# sch_knx-valve-control_v1_2.net
KiCad netlist of a schematic drawn in EasyEDA
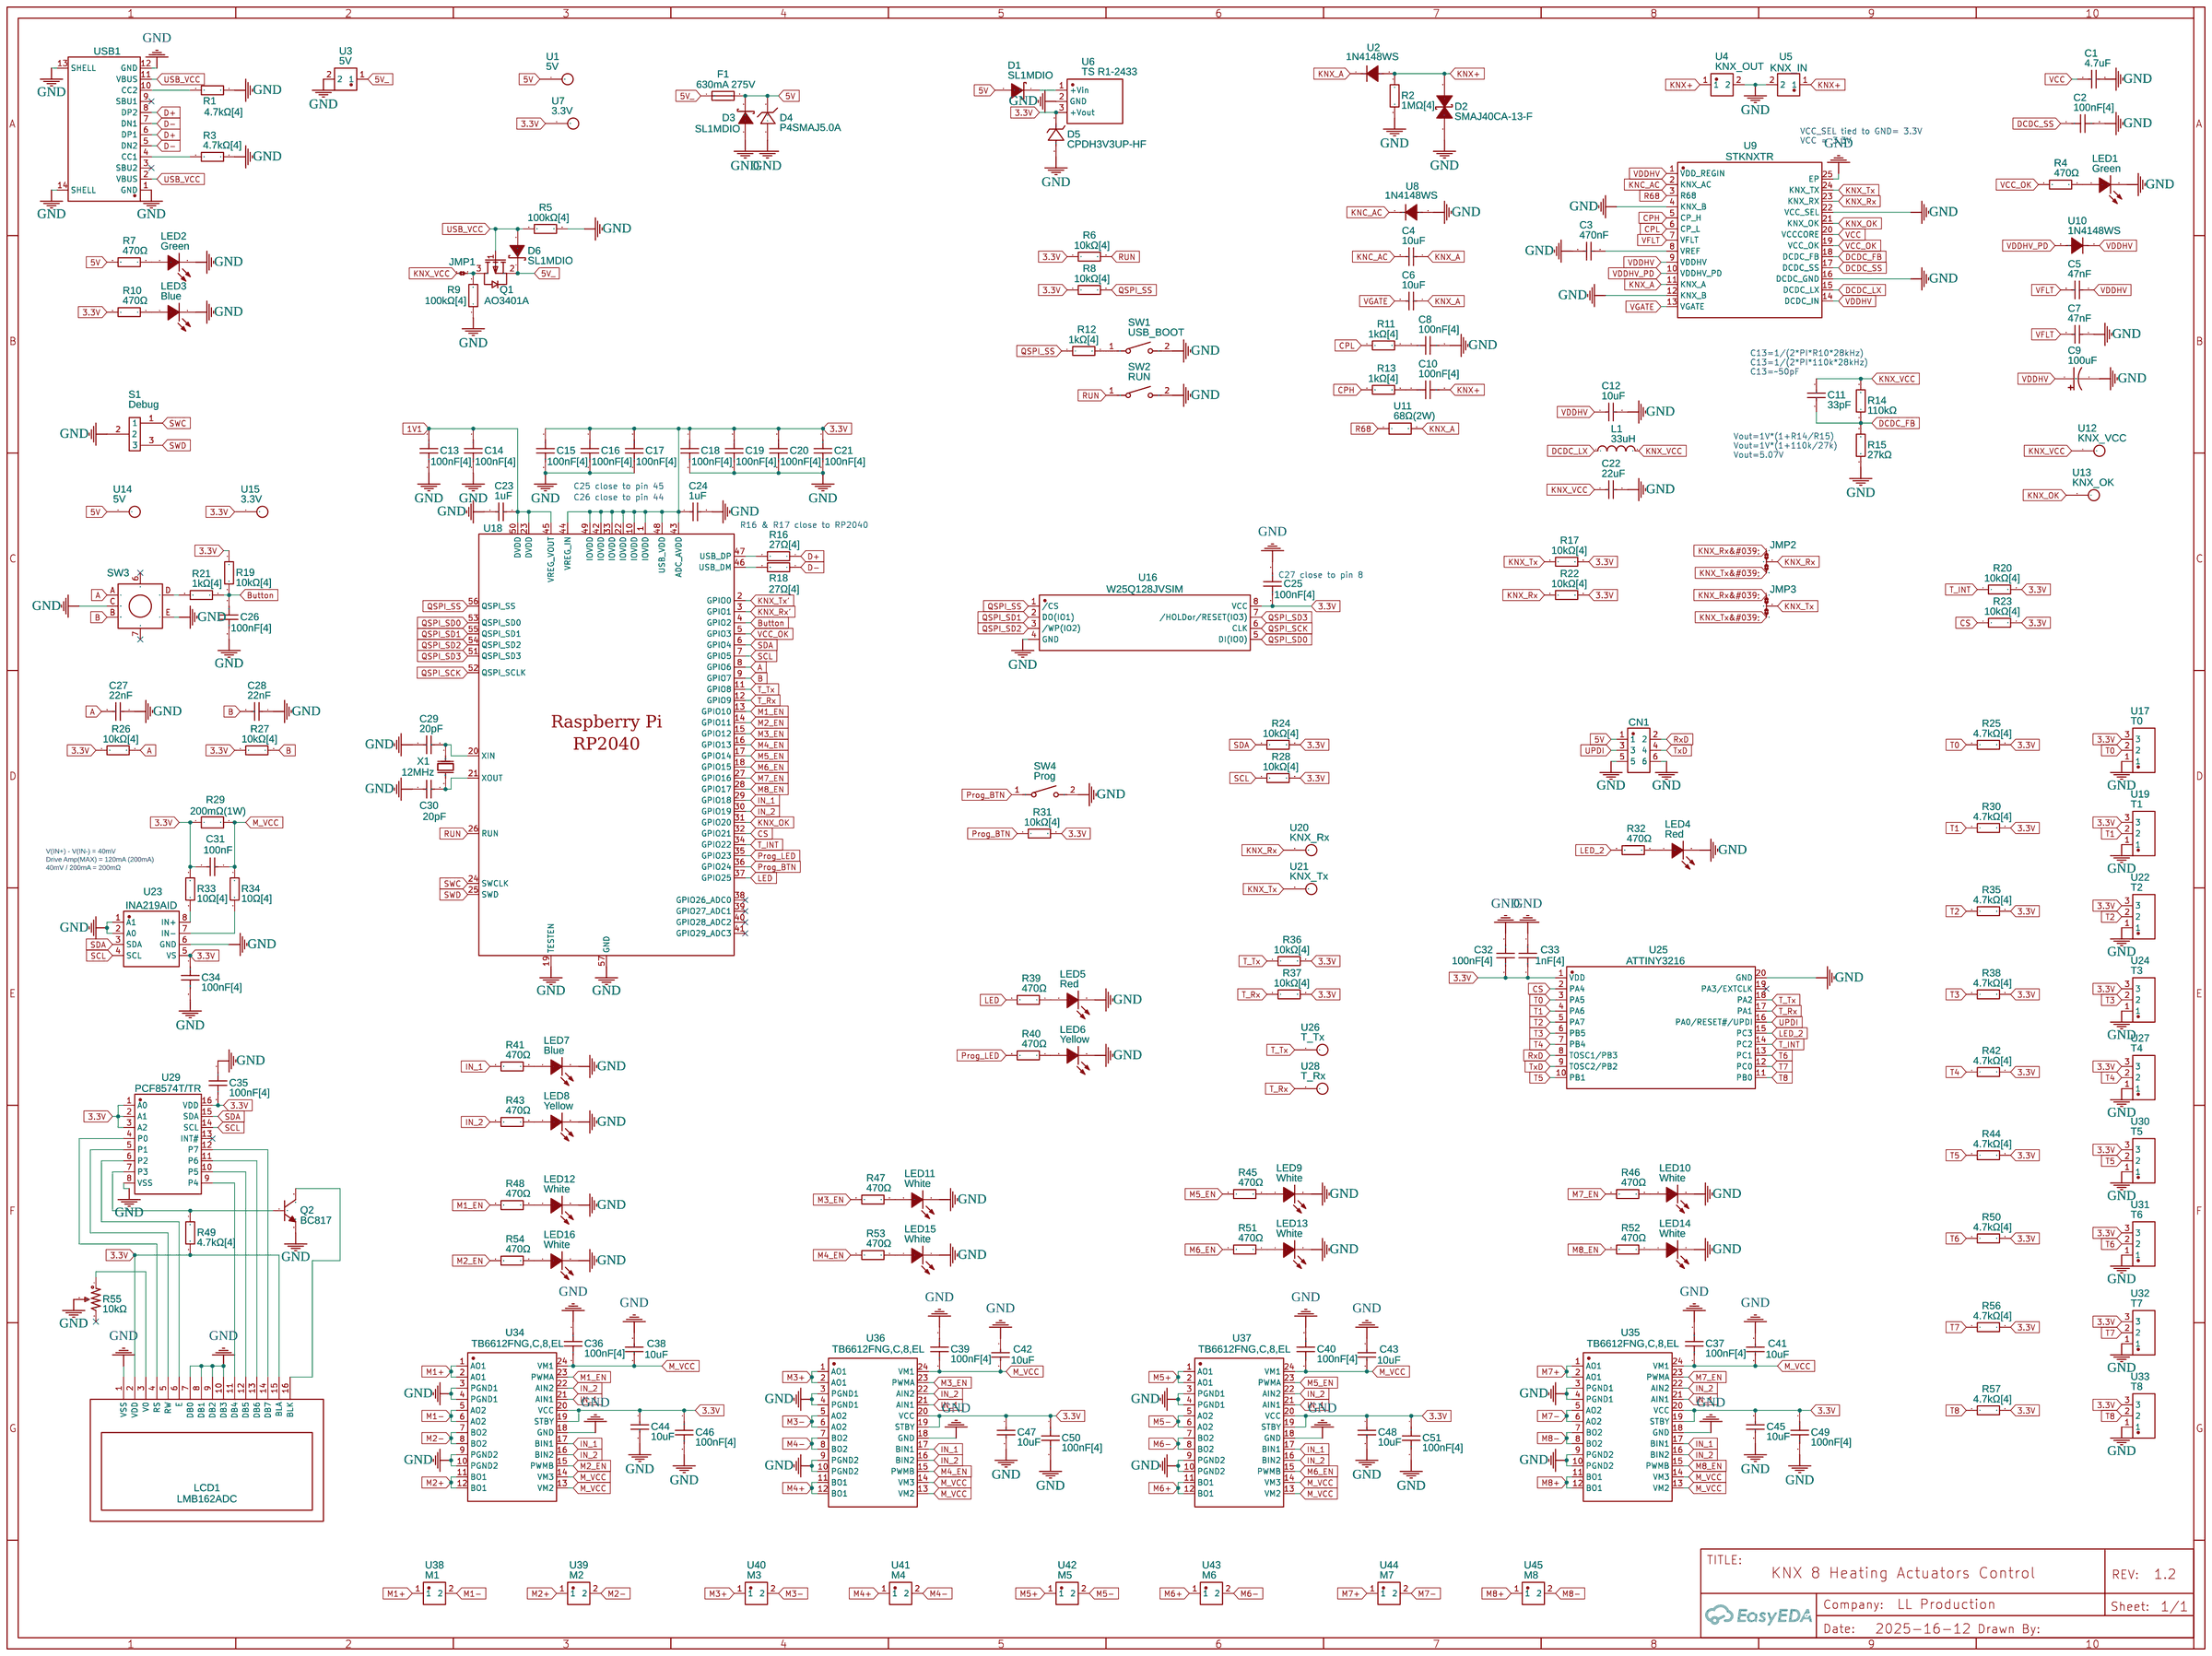
[diagram p0: schematic sheet]

(export (version "E")
  (design (tool "Eeschema 10.0.6"))
  (components
    (comp (ref "C1")
      (value "4.7uF")
      (fields (field (name "Manufacturer Part") "CC0603KRX7R9BB103") (field (name "Manufacturer") "YAGEO"))
      (libsource (lib "") (part "CC0603KRX7R9BB103_2"))
    )
    (comp (ref "C2")
      (value "100nF[4]")
      (fields
        (field (name "Manufacturer Part") "GRM155R71H104KE14D")
        (field (name "Manufacturer") "muRata(村田)")
      )
      (libsource (lib "") (part "GRM155R71H104KE14D_1"))
    )
    (comp (ref "C3")
      (value "470nF")
      (fields (field (name "Manufacturer Part") "CC0603KRX7R9BB103") (field (name "Manufacturer") "YAGEO"))
      (libsource (lib "") (part "CC0603KRX7R9BB103_1"))
    )
    (comp (ref "C4")
      (value "10uF")
      (fields (field (name "Manufacturer Part") "CC0603KRX7R9BB103") (field (name "Manufacturer") "YAGEO"))
      (libsource (lib "") (part "CC0603KRX7R9BB103_2"))
    )
    (comp (ref "C5")
      (value "47nF")
      (fields (field (name "Manufacturer Part") "CC0603KRX7R9BB103") (field (name "Manufacturer") "YAGEO"))
      (libsource (lib "") (part "CC0603KRX7R9BB103_2"))
    )
    (comp (ref "C6")
      (value "10uF")
      (fields (field (name "Manufacturer Part") "CC0603KRX7R9BB103") (field (name "Manufacturer") "YAGEO"))
      (libsource (lib "") (part "CC0603KRX7R9BB103_2"))
    )
    (comp (ref "C7")
      (value "47nF")
      (fields (field (name "Manufacturer Part") "CC0603KRX7R9BB103") (field (name "Manufacturer") "YAGEO"))
      (libsource (lib "") (part "CC0603KRX7R9BB103_2"))
    )
    (comp (ref "C8")
      (value "100nF[4]")
      (fields
        (field (name "Manufacturer Part") "GRM155R71H104KE14D")
        (field (name "Manufacturer") "muRata(村田)")
      )
      (libsource (lib "") (part "GRM155R71H104KE14D_1"))
    )
    (comp (ref "C9")
      (value "100uF")
      (fields (field (name "Manufacturer Part") "VEJ101M1HTR-0810") (field (name "Manufacturer") "Lelon(立隆)"))
      (libsource (lib "") (part "VEJ101M1HTR-0810"))
    )
    (comp (ref "C10")
      (value "100nF[4]")
      (fields
        (field (name "Manufacturer Part") "GRM155R71H104KE14D")
        (field (name "Manufacturer") "muRata(村田)")
      )
      (libsource (lib "") (part "GRM155R71H104KE14D_1"))
    )
    (comp (ref "C11")
      (value "33pF")
      (fields (field (name "Manufacturer Part") "CC0603KRX7R9BB103") (field (name "Manufacturer") "YAGEO"))
      (libsource (lib "") (part "CC0603KRX7R9BB103"))
    )
    (comp (ref "C12")
      (value "10uF")
      (fields (field (name "Manufacturer Part") "CC0603KRX7R9BB103") (field (name "Manufacturer") "YAGEO"))
      (libsource (lib "") (part "CC0603KRX7R9BB103_1"))
    )
    (comp (ref "C13")
      (value "100nF[4]")
      (fields
        (field (name "Manufacturer Part") "GRM155R71H104KE14D")
        (field (name "Manufacturer") "muRata(村田)")
      )
      (libsource (lib "") (part "GRM155R71H104KE14D"))
    )
    (comp (ref "C14")
      (value "100nF[4]")
      (fields
        (field (name "Manufacturer Part") "GRM155R71H104KE14D")
        (field (name "Manufacturer") "muRata(村田)")
      )
      (libsource (lib "") (part "GRM155R71H104KE14D"))
    )
    (comp (ref "C15")
      (value "100nF[4]")
      (fields
        (field (name "Manufacturer Part") "GRM155R71H104KE14D")
        (field (name "Manufacturer") "muRata(村田)")
      )
      (libsource (lib "") (part "GRM155R71H104KE14D"))
    )
    (comp (ref "C16")
      (value "100nF[4]")
      (fields
        (field (name "Manufacturer Part") "GRM155R71H104KE14D")
        (field (name "Manufacturer") "muRata(村田)")
      )
      (libsource (lib "") (part "GRM155R71H104KE14D"))
    )
    (comp (ref "C17")
      (value "100nF[4]")
      (fields
        (field (name "Manufacturer Part") "GRM155R71H104KE14D")
        (field (name "Manufacturer") "muRata(村田)")
      )
      (libsource (lib "") (part "GRM155R71H104KE14D"))
    )
    (comp (ref "C18")
      (value "100nF[4]")
      (fields
        (field (name "Manufacturer Part") "GRM155R71H104KE14D")
        (field (name "Manufacturer") "muRata(村田)")
      )
      (libsource (lib "") (part "GRM155R71H104KE14D"))
    )
    (comp (ref "C19")
      (value "100nF[4]")
      (fields
        (field (name "Manufacturer Part") "GRM155R71H104KE14D")
        (field (name "Manufacturer") "muRata(村田)")
      )
      (libsource (lib "") (part "GRM155R71H104KE14D"))
    )
    (comp (ref "C20")
      (value "100nF[4]")
      (fields
        (field (name "Manufacturer Part") "GRM155R71H104KE14D")
        (field (name "Manufacturer") "muRata(村田)")
      )
      (libsource (lib "") (part "GRM155R71H104KE14D"))
    )
    (comp (ref "C21")
      (value "100nF[4]")
      (fields
        (field (name "Manufacturer Part") "GRM155R71H104KE14D")
        (field (name "Manufacturer") "muRata(村田)")
      )
      (libsource (lib "") (part "GRM155R71H104KE14D"))
    )
    (comp (ref "C22")
      (value "22uF")
      (fields (field (name "Manufacturer Part") "CC0603KRX7R9BB103") (field (name "Manufacturer") "YAGEO"))
      (libsource (lib "") (part "CC0603KRX7R9BB103_1"))
    )
    (comp (ref "C23")
      (value "1uF")
      (fields (field (name "Manufacturer Part") "CC0603KRX7R9BB103") (field (name "Manufacturer") "YAGEO"))
      (libsource (lib "") (part "CC0603KRX7R9BB103_1"))
    )
    (comp (ref "C24")
      (value "1uF")
      (fields (field (name "Manufacturer Part") "CC0603KRX7R9BB103") (field (name "Manufacturer") "YAGEO"))
      (libsource (lib "") (part "CC0603KRX7R9BB103_1"))
    )
    (comp (ref "C25")
      (value "100nF[4]")
      (fields
        (field (name "Manufacturer Part") "GRM155R71H104KE14D")
        (field (name "Manufacturer") "muRata(村田)")
      )
      (libsource (lib "") (part "GRM155R71H104KE14D"))
    )
    (comp (ref "C26")
      (value "100nF[4]")
      (fields
        (field (name "Manufacturer Part") "GRM155R71H104KE14D")
        (field (name "Manufacturer") "muRata(村田)")
      )
      (libsource (lib "") (part "GRM155R71H104KE14D"))
    )
    (comp (ref "C27")
      (value "22nF")
      (fields (field (name "Manufacturer Part") "CC0603KRX7R9BB103") (field (name "Manufacturer") "YAGEO"))
      (libsource (lib "") (part "CC0603KRX7R9BB103_2"))
    )
    (comp (ref "C28")
      (value "22nF")
      (fields (field (name "Manufacturer Part") "CC0603KRX7R9BB103") (field (name "Manufacturer") "YAGEO"))
      (libsource (lib "") (part "CC0603KRX7R9BB103_2"))
    )
    (comp (ref "C29")
      (value "20pF")
      (fields (field (name "Manufacturer Part") "CC0603KRX7R9BB103") (field (name "Manufacturer") "YAGEO"))
      (libsource (lib "") (part "CC0603KRX7R9BB103_1"))
    )
    (comp (ref "C30")
      (value "20pF")
      (fields (field (name "Manufacturer Part") "CC0603KRX7R9BB103") (field (name "Manufacturer") "YAGEO"))
      (libsource (lib "") (part "CC0603KRX7R9BB103_1"))
    )
    (comp (ref "C31")
      (value "100nF")
      (fields (field (name "Manufacturer Part") "CC0603KRX7R9BB103") (field (name "Manufacturer") "YAGEO"))
      (libsource (lib "") (part "CC0603KRX7R9BB103_2"))
    )
    (comp (ref "C32")
      (value "100nF[4]")
      (fields
        (field (name "Manufacturer Part") "GRM155R71H104KE14D")
        (field (name "Manufacturer") "muRata(村田)")
      )
      (libsource (lib "") (part "GRM155R71H104KE14D"))
    )
    (comp (ref "C33")
      (value "1nF[4]")
      (fields
        (field (name "Manufacturer Part") "GRM155R71H104KE14D")
        (field (name "Manufacturer") "muRata(村田)")
      )
      (libsource (lib "") (part "GRM155R71H104KE14D"))
    )
    (comp (ref "C34")
      (value "100nF[4]")
      (fields
        (field (name "Manufacturer Part") "GRM155R71H104KE14D")
        (field (name "Manufacturer") "muRata(村田)")
      )
      (libsource (lib "") (part "GRM155R71H104KE14D"))
    )
    (comp (ref "C35")
      (value "100nF[4]")
      (fields
        (field (name "Manufacturer Part") "GRM155R71H104KE14D")
        (field (name "Manufacturer") "muRata(村田)")
      )
      (libsource (lib "") (part "GRM155R71H104KE14D"))
    )
    (comp (ref "C36")
      (value "100nF[4]")
      (fields
        (field (name "Manufacturer Part") "GRM155R71H104KE14D")
        (field (name "Manufacturer") "muRata(村田)")
      )
      (libsource (lib "") (part "GRM155R71H104KE14D"))
    )
    (comp (ref "C37")
      (value "100nF[4]")
      (fields
        (field (name "Manufacturer Part") "GRM155R71H104KE14D")
        (field (name "Manufacturer") "muRata(村田)")
      )
      (libsource (lib "") (part "GRM155R71H104KE14D"))
    )
    (comp (ref "C38")
      (value "10uF")
      (fields (field (name "Manufacturer Part") "CC0603KRX7R9BB103") (field (name "Manufacturer") "YAGEO"))
      (libsource (lib "") (part "CC0603KRX7R9BB103"))
    )
    (comp (ref "C39")
      (value "100nF[4]")
      (fields
        (field (name "Manufacturer Part") "GRM155R71H104KE14D")
        (field (name "Manufacturer") "muRata(村田)")
      )
      (libsource (lib "") (part "GRM155R71H104KE14D"))
    )
    (comp (ref "C40")
      (value "100nF[4]")
      (fields
        (field (name "Manufacturer Part") "GRM155R71H104KE14D")
        (field (name "Manufacturer") "muRata(村田)")
      )
      (libsource (lib "") (part "GRM155R71H104KE14D"))
    )
    (comp (ref "C41")
      (value "10uF")
      (fields (field (name "Manufacturer Part") "CC0603KRX7R9BB103") (field (name "Manufacturer") "YAGEO"))
      (libsource (lib "") (part "CC0603KRX7R9BB103"))
    )
    (comp (ref "C42")
      (value "10uF")
      (fields (field (name "Manufacturer Part") "CC0603KRX7R9BB103") (field (name "Manufacturer") "YAGEO"))
      (libsource (lib "") (part "CC0603KRX7R9BB103"))
    )
    (comp (ref "C43")
      (value "10uF")
      (fields (field (name "Manufacturer Part") "CC0603KRX7R9BB103") (field (name "Manufacturer") "YAGEO"))
      (libsource (lib "") (part "CC0603KRX7R9BB103"))
    )
    (comp (ref "C44")
      (value "10uF")
      (fields (field (name "Manufacturer Part") "CC0603KRX7R9BB103") (field (name "Manufacturer") "YAGEO"))
      (libsource (lib "") (part "CC0603KRX7R9BB103"))
    )
    (comp (ref "C45")
      (value "10uF")
      (fields (field (name "Manufacturer Part") "CC0603KRX7R9BB103") (field (name "Manufacturer") "YAGEO"))
      (libsource (lib "") (part "CC0603KRX7R9BB103"))
    )
    (comp (ref "C46")
      (value "100nF[4]")
      (fields
        (field (name "Manufacturer Part") "GRM155R71H104KE14D")
        (field (name "Manufacturer") "muRata(村田)")
      )
      (libsource (lib "") (part "GRM155R71H104KE14D"))
    )
    (comp (ref "C47")
      (value "10uF")
      (fields (field (name "Manufacturer Part") "CC0603KRX7R9BB103") (field (name "Manufacturer") "YAGEO"))
      (libsource (lib "") (part "CC0603KRX7R9BB103"))
    )
    (comp (ref "C48")
      (value "10uF")
      (fields (field (name "Manufacturer Part") "CC0603KRX7R9BB103") (field (name "Manufacturer") "YAGEO"))
      (libsource (lib "") (part "CC0603KRX7R9BB103"))
    )
    (comp (ref "C49")
      (value "100nF[4]")
      (fields
        (field (name "Manufacturer Part") "GRM155R71H104KE14D")
        (field (name "Manufacturer") "muRata(村田)")
      )
      (libsource (lib "") (part "GRM155R71H104KE14D"))
    )
    (comp (ref "C50")
      (value "100nF[4]")
      (fields
        (field (name "Manufacturer Part") "GRM155R71H104KE14D")
        (field (name "Manufacturer") "muRata(村田)")
      )
      (libsource (lib "") (part "GRM155R71H104KE14D"))
    )
    (comp (ref "C51")
      (value "100nF[4]")
      (fields
        (field (name "Manufacturer Part") "GRM155R71H104KE14D")
        (field (name "Manufacturer") "muRata(村田)")
      )
      (libsource (lib "") (part "GRM155R71H104KE14D"))
    )
    (comp (ref "CN1")
      (value "321006SG0ABK00A01")
      (fields (field (name "Manufacturer") "JILN(锦凌)"))
      (libsource (lib "") (part "321006SG0ABK00A01"))
    )
    (comp (ref "D1")
      (value "SL1MDIO")
      (fields (field (name "Manufacturer Part") "1N5819HW-7-F") (field (name "Manufacturer") "DIODES(美台)"))
      (libsource (lib "") (part "1N5819HW-7-F_2"))
    )
    (comp (ref "D2")
      (value "SMAJ40CA-13-F")
      (fields (field (name "Manufacturer") "DIODES(美台)"))
      (libsource (lib "") (part "SMAJ40CA-13-F"))
    )
    (comp (ref "D3")
      (value "SL1MDIO")
      (fields (field (name "Manufacturer Part") "1N5819HW-7-F") (field (name "Manufacturer") "DIODES(美台)"))
      (libsource (lib "") (part "1N5819HW-7-F"))
    )
    (comp (ref "D4")
      (value "P4SMAJ5.0A")
      (fields
        (field (name "Manufacturer Part") "P4SMAJ12A_R1_00001")
        (field (name "Manufacturer") "PANJIT(强茂)")
      )
      (libsource (lib "") (part "P4SMAJ12A-PEC"))
    )
    (comp (ref "D5")
      (value "CPDH3V3UP-HF")
      (fields (field (name "Manufacturer Part") "SOD-523"))
      (libsource (lib "") (part "SOD-523"))
    )
    (comp (ref "D6")
      (value "SL1MDIO")
      (fields (field (name "Manufacturer Part") "1N5819HW-7-F") (field (name "Manufacturer") "DIODES(美台)"))
      (libsource (lib "") (part "1N5819HW-7-F_1"))
    )
    (comp (ref "F1")
      (value "630mA 275V")
      (fields (field (name "Manufacturer Part") "S1032-F-60.0A") (field (name "Manufacturer") "SART(萨特)"))
      (libsource (lib "") (part "S1032-F-60.0A"))
    )
    (comp (ref "JMP1") (value "Rx") (libsource (lib "") (part "JMP-2-NO-0603")))
    (comp (ref "JMP2") (value "JMP-3-NO-0402") (libsource (lib "") (part "JMP-3-NO-0402")))
    (comp (ref "JMP3") (value "JMP-3-NO-0402") (libsource (lib "") (part "JMP-3-NO-0402")))
    (comp (ref "L1")
      (value "33uH")
      (fields
        (field (name "Manufacturer Part") "NR5040T330M")
        (field (name "Manufacturer") "TAIYO YUDEN(太诱)")
      )
      (libsource (lib "") (part "NR5040T330M"))
    )
    (comp (ref "LCD1")
      (value "LMB162ADC")
      (fields (field (name "Manufacturer") "TOPWAY"))
      (libsource (lib "") (part "LMB162ADC"))
    )
    (comp (ref "LED1")
      (value "Green")
      (fields (field (name "Manufacturer Part") "SZYY0603R") (field (name "Manufacturer") "yongyu(永裕光电)"))
      (libsource (lib "") (part "SZYY0603R"))
    )
    (comp (ref "LED2")
      (value "Green")
      (fields (field (name "Manufacturer Part") "SZYY0603R") (field (name "Manufacturer") "yongyu(永裕光电)"))
      (libsource (lib "") (part "SZYY0603R"))
    )
    (comp (ref "LED3")
      (value "Blue")
      (fields (field (name "Manufacturer Part") "SZYY0603R") (field (name "Manufacturer") "yongyu(永裕光电)"))
      (libsource (lib "") (part "SZYY0603R"))
    )
    (comp (ref "LED4")
      (value "Red")
      (fields (field (name "Manufacturer Part") "SZYY0603R") (field (name "Manufacturer") "yongyu(永裕光电)"))
      (libsource (lib "") (part "SZYY0603R"))
    )
    (comp (ref "LED5")
      (value "Red")
      (fields (field (name "Manufacturer Part") "SZYY0603R") (field (name "Manufacturer") "yongyu(永裕光电)"))
      (libsource (lib "") (part "SZYY0603R"))
    )
    (comp (ref "LED6")
      (value "Yellow")
      (fields (field (name "Manufacturer Part") "SZYY0603R") (field (name "Manufacturer") "yongyu(永裕光电)"))
      (libsource (lib "") (part "SZYY0603R"))
    )
    (comp (ref "LED7")
      (value "Blue")
      (fields (field (name "Manufacturer Part") "SZYY0603R") (field (name "Manufacturer") "yongyu(永裕光电)"))
      (libsource (lib "") (part "SZYY0603R"))
    )
    (comp (ref "LED8")
      (value "Yellow")
      (fields (field (name "Manufacturer Part") "SZYY0603R") (field (name "Manufacturer") "yongyu(永裕光电)"))
      (libsource (lib "") (part "SZYY0603R"))
    )
    (comp (ref "LED9")
      (value "White")
      (fields (field (name "Manufacturer Part") "SZYY0603R") (field (name "Manufacturer") "yongyu(永裕光电)"))
      (libsource (lib "") (part "SZYY0603R"))
    )
    (comp (ref "LED10")
      (value "White")
      (fields (field (name "Manufacturer Part") "SZYY0603R") (field (name "Manufacturer") "yongyu(永裕光电)"))
      (libsource (lib "") (part "SZYY0603R"))
    )
    (comp (ref "LED11")
      (value "White")
      (fields (field (name "Manufacturer Part") "SZYY0603R") (field (name "Manufacturer") "yongyu(永裕光电)"))
      (libsource (lib "") (part "SZYY0603R"))
    )
    (comp (ref "LED12")
      (value "White")
      (fields (field (name "Manufacturer Part") "SZYY0603R") (field (name "Manufacturer") "yongyu(永裕光电)"))
      (libsource (lib "") (part "SZYY0603R"))
    )
    (comp (ref "LED13")
      (value "White")
      (fields (field (name "Manufacturer Part") "SZYY0603R") (field (name "Manufacturer") "yongyu(永裕光电)"))
      (libsource (lib "") (part "SZYY0603R"))
    )
    (comp (ref "LED14")
      (value "White")
      (fields (field (name "Manufacturer Part") "SZYY0603R") (field (name "Manufacturer") "yongyu(永裕光电)"))
      (libsource (lib "") (part "SZYY0603R"))
    )
    (comp (ref "LED15")
      (value "White")
      (fields (field (name "Manufacturer Part") "SZYY0603R") (field (name "Manufacturer") "yongyu(永裕光电)"))
      (libsource (lib "") (part "SZYY0603R"))
    )
    (comp (ref "LED16")
      (value "White")
      (fields (field (name "Manufacturer Part") "SZYY0603R") (field (name "Manufacturer") "yongyu(永裕光电)"))
      (libsource (lib "") (part "SZYY0603R"))
    )
    (comp (ref "Q1")
      (value "AO3401A")
      (fields (field (name "Manufacturer") "HUASHUO(华朔)"))
      (libsource (lib "") (part "AO3401A_C700954"))
    )
    (comp (ref "Q2")
      (value "BC817")
      (fields (field (name "Manufacturer Part") "BC817-40,215") (field (name "Manufacturer") "Nexperia(安世)"))
      (libsource (lib "") (part "BC817-40,215"))
    )
    (comp (ref "R1")
      (value "4.7kΩ[4]")
      (fields
        (field (name "Manufacturer Part") "0402WGF1002TCE")
        (field (name "Manufacturer") "UNI-ROYAL(厚声)")
      )
      (libsource (lib "") (part "0402WGF1002TCE"))
    )
    (comp (ref "R2")
      (value "1MΩ[4]")
      (fields
        (field (name "Manufacturer Part") "0402WGF1002TCE")
        (field (name "Manufacturer") "UNI-ROYAL(厚声)")
      )
      (libsource (lib "") (part "0402WGF1002TCE_2"))
    )
    (comp (ref "R3")
      (value "4.7kΩ[4]")
      (fields
        (field (name "Manufacturer Part") "0402WGF1002TCE")
        (field (name "Manufacturer") "UNI-ROYAL(厚声)")
      )
      (libsource (lib "") (part "0402WGF1002TCE"))
    )
    (comp (ref "R4")
      (value "470Ω")
      (fields (field (name "Manufacturer Part") "CR0603FA1001G") (field (name "Manufacturer") "LIZ(丽智电子)"))
      (libsource (lib "") (part "CR0603FA1001G_C126900"))
    )
    (comp (ref "R5")
      (value "100kΩ[4]")
      (fields
        (field (name "Manufacturer Part") "0402WGF1002TCE")
        (field (name "Manufacturer") "UNI-ROYAL(厚声)")
      )
      (libsource (lib "") (part "0402WGF1002TCE_1"))
    )
    (comp (ref "R6")
      (value "10kΩ[4]")
      (fields
        (field (name "Manufacturer Part") "0402WGF1002TCE")
        (field (name "Manufacturer") "UNI-ROYAL(厚声)")
      )
      (libsource (lib "") (part "0402WGF1002TCE_1"))
    )
    (comp (ref "R7")
      (value "470Ω")
      (fields (field (name "Manufacturer Part") "CR0603FA1001G") (field (name "Manufacturer") "LIZ(丽智电子)"))
      (libsource (lib "") (part "CR0603FA1001G_C126900"))
    )
    (comp (ref "R8")
      (value "10kΩ[4]")
      (fields
        (field (name "Manufacturer Part") "0402WGF1002TCE")
        (field (name "Manufacturer") "UNI-ROYAL(厚声)")
      )
      (libsource (lib "") (part "0402WGF1002TCE_1"))
    )
    (comp (ref "R9")
      (value "100kΩ[4]")
      (fields
        (field (name "Manufacturer Part") "0402WGF1002TCE")
        (field (name "Manufacturer") "UNI-ROYAL(厚声)")
      )
      (libsource (lib "") (part "0402WGF1002TCE_3"))
    )
    (comp (ref "R10")
      (value "470Ω")
      (fields (field (name "Manufacturer Part") "CR0603FA1001G") (field (name "Manufacturer") "LIZ(丽智电子)"))
      (libsource (lib "") (part "CR0603FA1001G_C126900"))
    )
    (comp (ref "R11")
      (value "1kΩ[4]")
      (fields
        (field (name "Manufacturer Part") "0402WGF1002TCE")
        (field (name "Manufacturer") "UNI-ROYAL(厚声)")
      )
      (libsource (lib "") (part "0402WGF1002TCE_1"))
    )
    (comp (ref "R12")
      (value "1kΩ[4]")
      (fields
        (field (name "Manufacturer Part") "0402WGF1002TCE")
        (field (name "Manufacturer") "UNI-ROYAL(厚声)")
      )
      (libsource (lib "") (part "0402WGF1002TCE_1"))
    )
    (comp (ref "R13")
      (value "1kΩ[4]")
      (fields
        (field (name "Manufacturer Part") "0402WGF1002TCE")
        (field (name "Manufacturer") "UNI-ROYAL(厚声)")
      )
      (libsource (lib "") (part "0402WGF1002TCE_1"))
    )
    (comp (ref "R14")
      (value "110kΩ")
      (fields (field (name "Manufacturer Part") "CR0603FA1001G") (field (name "Manufacturer") "LIZ(丽智电子)"))
      (libsource (lib "") (part "CR0603FA1001G_C126900_1"))
    )
    (comp (ref "R15")
      (value "27kΩ")
      (fields (field (name "Manufacturer Part") "CR0603FA1001G") (field (name "Manufacturer") "LIZ(丽智电子)"))
      (libsource (lib "") (part "CR0603FA1001G_C126900_1"))
    )
    (comp (ref "R16")
      (value "27Ω[4]")
      (fields
        (field (name "Manufacturer Part") "0402WGF1002TCE")
        (field (name "Manufacturer") "UNI-ROYAL(厚声)")
      )
      (libsource (lib "") (part "0402WGF1002TCE"))
    )
    (comp (ref "R17")
      (value "10kΩ[4]")
      (fields
        (field (name "Manufacturer Part") "0402WGF1002TCE")
        (field (name "Manufacturer") "UNI-ROYAL(厚声)")
      )
      (libsource (lib "") (part "0402WGF1002TCE_1"))
    )
    (comp (ref "R18")
      (value "27Ω[4]")
      (fields
        (field (name "Manufacturer Part") "0402WGF1002TCE")
        (field (name "Manufacturer") "UNI-ROYAL(厚声)")
      )
      (libsource (lib "") (part "0402WGF1002TCE"))
    )
    (comp (ref "R19")
      (value "10kΩ[4]")
      (fields
        (field (name "Manufacturer Part") "0402WGF1002TCE")
        (field (name "Manufacturer") "UNI-ROYAL(厚声)")
      )
      (libsource (lib "") (part "0402WGF1002TCE_2"))
    )
    (comp (ref "R20")
      (value "10kΩ[4]")
      (fields
        (field (name "Manufacturer Part") "0402WGF1002TCE")
        (field (name "Manufacturer") "UNI-ROYAL(厚声)")
      )
      (libsource (lib "") (part "0402WGF1002TCE_1"))
    )
    (comp (ref "R21")
      (value "1kΩ[4]")
      (fields
        (field (name "Manufacturer Part") "0402WGF1002TCE")
        (field (name "Manufacturer") "UNI-ROYAL(厚声)")
      )
      (libsource (lib "") (part "0402WGF1002TCE"))
    )
    (comp (ref "R22")
      (value "10kΩ[4]")
      (fields
        (field (name "Manufacturer Part") "0402WGF1002TCE")
        (field (name "Manufacturer") "UNI-ROYAL(厚声)")
      )
      (libsource (lib "") (part "0402WGF1002TCE_1"))
    )
    (comp (ref "R23")
      (value "10kΩ[4]")
      (fields
        (field (name "Manufacturer Part") "0402WGF1002TCE")
        (field (name "Manufacturer") "UNI-ROYAL(厚声)")
      )
      (libsource (lib "") (part "0402WGF1002TCE_1"))
    )
    (comp (ref "R24")
      (value "10kΩ[4]")
      (fields
        (field (name "Manufacturer Part") "0402WGF1002TCE")
        (field (name "Manufacturer") "UNI-ROYAL(厚声)")
      )
      (libsource (lib "") (part "0402WGF1002TCE_1"))
    )
    (comp (ref "R25")
      (value "4.7kΩ[4]")
      (fields
        (field (name "Manufacturer Part") "0402WGF1002TCE")
        (field (name "Manufacturer") "UNI-ROYAL(厚声)")
      )
      (libsource (lib "") (part "0402WGF1002TCE_1"))
    )
    (comp (ref "R26")
      (value "10kΩ[4]")
      (fields
        (field (name "Manufacturer Part") "0402WGF1002TCE")
        (field (name "Manufacturer") "UNI-ROYAL(厚声)")
      )
      (libsource (lib "") (part "0402WGF1002TCE_1"))
    )
    (comp (ref "R27")
      (value "10kΩ[4]")
      (fields
        (field (name "Manufacturer Part") "0402WGF1002TCE")
        (field (name "Manufacturer") "UNI-ROYAL(厚声)")
      )
      (libsource (lib "") (part "0402WGF1002TCE_1"))
    )
    (comp (ref "R28")
      (value "10kΩ[4]")
      (fields
        (field (name "Manufacturer Part") "0402WGF1002TCE")
        (field (name "Manufacturer") "UNI-ROYAL(厚声)")
      )
      (libsource (lib "") (part "0402WGF1002TCE_1"))
    )
    (comp (ref "R29")
      (value "200mΩ(1W)")
      (fields (field (name "Manufacturer Part") "SCR1206F1M1") (field (name "Manufacturer") "VO(翔胜)"))
      (libsource (lib "") (part "SCR1206F1M1"))
    )
    (comp (ref "R30")
      (value "4.7kΩ[4]")
      (fields
        (field (name "Manufacturer Part") "0402WGF1002TCE")
        (field (name "Manufacturer") "UNI-ROYAL(厚声)")
      )
      (libsource (lib "") (part "0402WGF1002TCE_1"))
    )
    (comp (ref "R31")
      (value "10kΩ[4]")
      (fields
        (field (name "Manufacturer Part") "0402WGF1002TCE")
        (field (name "Manufacturer") "UNI-ROYAL(厚声)")
      )
      (libsource (lib "") (part "0402WGF1002TCE_1"))
    )
    (comp (ref "R32")
      (value "470Ω")
      (fields (field (name "Manufacturer Part") "CR0603FA1001G") (field (name "Manufacturer") "LIZ(丽智电子)"))
      (libsource (lib "") (part "CR0603FA1001G_C126900"))
    )
    (comp (ref "R33")
      (value "10Ω[4]")
      (fields
        (field (name "Manufacturer Part") "0402WGF1002TCE")
        (field (name "Manufacturer") "UNI-ROYAL(厚声)")
      )
      (libsource (lib "") (part "0402WGF1002TCE_2"))
    )
    (comp (ref "R34")
      (value "10Ω[4]")
      (fields
        (field (name "Manufacturer Part") "0402WGF1002TCE")
        (field (name "Manufacturer") "UNI-ROYAL(厚声)")
      )
      (libsource (lib "") (part "0402WGF1002TCE_2"))
    )
    (comp (ref "R35")
      (value "4.7kΩ[4]")
      (fields
        (field (name "Manufacturer Part") "0402WGF1002TCE")
        (field (name "Manufacturer") "UNI-ROYAL(厚声)")
      )
      (libsource (lib "") (part "0402WGF1002TCE_1"))
    )
    (comp (ref "R36")
      (value "10kΩ[4]")
      (fields
        (field (name "Manufacturer Part") "0402WGF1002TCE")
        (field (name "Manufacturer") "UNI-ROYAL(厚声)")
      )
      (libsource (lib "") (part "0402WGF1002TCE_1"))
    )
    (comp (ref "R37")
      (value "10kΩ[4]")
      (fields
        (field (name "Manufacturer Part") "0402WGF1002TCE")
        (field (name "Manufacturer") "UNI-ROYAL(厚声)")
      )
      (libsource (lib "") (part "0402WGF1002TCE_1"))
    )
    (comp (ref "R38")
      (value "4.7kΩ[4]")
      (fields
        (field (name "Manufacturer Part") "0402WGF1002TCE")
        (field (name "Manufacturer") "UNI-ROYAL(厚声)")
      )
      (libsource (lib "") (part "0402WGF1002TCE_1"))
    )
    (comp (ref "R39")
      (value "470Ω")
      (fields (field (name "Manufacturer Part") "CR0603FA1001G") (field (name "Manufacturer") "LIZ(丽智电子)"))
      (libsource (lib "") (part "CR0603FA1001G_C126900"))
    )
    (comp (ref "R40")
      (value "470Ω")
      (fields (field (name "Manufacturer Part") "CR0603FA1001G") (field (name "Manufacturer") "LIZ(丽智电子)"))
      (libsource (lib "") (part "CR0603FA1001G_C126900"))
    )
    (comp (ref "R41")
      (value "470Ω")
      (fields (field (name "Manufacturer Part") "CR0603FA1001G") (field (name "Manufacturer") "LIZ(丽智电子)"))
      (libsource (lib "") (part "CR0603FA1001G_C126900"))
    )
    (comp (ref "R42")
      (value "4.7kΩ[4]")
      (fields
        (field (name "Manufacturer Part") "0402WGF1002TCE")
        (field (name "Manufacturer") "UNI-ROYAL(厚声)")
      )
      (libsource (lib "") (part "0402WGF1002TCE_1"))
    )
    (comp (ref "R43")
      (value "470Ω")
      (fields (field (name "Manufacturer Part") "CR0603FA1001G") (field (name "Manufacturer") "LIZ(丽智电子)"))
      (libsource (lib "") (part "CR0603FA1001G_C126900"))
    )
    (comp (ref "R44")
      (value "4.7kΩ[4]")
      (fields
        (field (name "Manufacturer Part") "0402WGF1002TCE")
        (field (name "Manufacturer") "UNI-ROYAL(厚声)")
      )
      (libsource (lib "") (part "0402WGF1002TCE_1"))
    )
    (comp (ref "R45")
      (value "470Ω")
      (fields (field (name "Manufacturer Part") "CR0603FA1001G") (field (name "Manufacturer") "LIZ(丽智电子)"))
      (libsource (lib "") (part "CR0603FA1001G_C126900"))
    )
    (comp (ref "R46")
      (value "470Ω")
      (fields (field (name "Manufacturer Part") "CR0603FA1001G") (field (name "Manufacturer") "LIZ(丽智电子)"))
      (libsource (lib "") (part "CR0603FA1001G_C126900"))
    )
    (comp (ref "R47")
      (value "470Ω")
      (fields (field (name "Manufacturer Part") "CR0603FA1001G") (field (name "Manufacturer") "LIZ(丽智电子)"))
      (libsource (lib "") (part "CR0603FA1001G_C126900"))
    )
    (comp (ref "R48")
      (value "470Ω")
      (fields (field (name "Manufacturer Part") "CR0603FA1001G") (field (name "Manufacturer") "LIZ(丽智电子)"))
      (libsource (lib "") (part "CR0603FA1001G_C126900"))
    )
    (comp (ref "R49")
      (value "4.7kΩ[4]")
      (fields
        (field (name "Manufacturer Part") "0402WGF1002TCE")
        (field (name "Manufacturer") "UNI-ROYAL(厚声)")
      )
      (libsource (lib "") (part "0402WGF1002TCE_2"))
    )
    (comp (ref "R50")
      (value "4.7kΩ[4]")
      (fields
        (field (name "Manufacturer Part") "0402WGF1002TCE")
        (field (name "Manufacturer") "UNI-ROYAL(厚声)")
      )
      (libsource (lib "") (part "0402WGF1002TCE_1"))
    )
    (comp (ref "R51")
      (value "470Ω")
      (fields (field (name "Manufacturer Part") "CR0603FA1001G") (field (name "Manufacturer") "LIZ(丽智电子)"))
      (libsource (lib "") (part "CR0603FA1001G_C126900"))
    )
    (comp (ref "R52")
      (value "470Ω")
      (fields (field (name "Manufacturer Part") "CR0603FA1001G") (field (name "Manufacturer") "LIZ(丽智电子)"))
      (libsource (lib "") (part "CR0603FA1001G_C126900"))
    )
    (comp (ref "R53")
      (value "470Ω")
      (fields (field (name "Manufacturer Part") "CR0603FA1001G") (field (name "Manufacturer") "LIZ(丽智电子)"))
      (libsource (lib "") (part "CR0603FA1001G_C126900"))
    )
    (comp (ref "R54")
      (value "470Ω")
      (fields (field (name "Manufacturer Part") "CR0603FA1001G") (field (name "Manufacturer") "LIZ(丽智电子)"))
      (libsource (lib "") (part "CR0603FA1001G_C126900"))
    )
    (comp (ref "R55")
      (value "10kΩ")
      (fields (field (name "Manufacturer Part") "TC33X-2-103E") (field (name "Manufacturer") "BOURNS"))
      (libsource (lib "") (part "TC33X-2-103E"))
    )
    (comp (ref "R56")
      (value "4.7kΩ[4]")
      (fields
        (field (name "Manufacturer Part") "0402WGF1002TCE")
        (field (name "Manufacturer") "UNI-ROYAL(厚声)")
      )
      (libsource (lib "") (part "0402WGF1002TCE_1"))
    )
    (comp (ref "R57")
      (value "4.7kΩ[4]")
      (fields
        (field (name "Manufacturer Part") "0402WGF1002TCE")
        (field (name "Manufacturer") "UNI-ROYAL(厚声)")
      )
      (libsource (lib "") (part "0402WGF1002TCE_1"))
    )
    (comp (ref "S1") (value "Debug") (libsource (lib "") (part "3PAD_SEL")))
    (comp (ref "SW1")
      (value "USB_BOOT")
      (fields
        (field (name "Manufacturer Part") "TS-1185EC-C-D-B")
        (field (name "Manufacturer") "XKB Connection(中国星坤)")
      )
      (libsource (lib "") (part "TS-1185EC-C-D-B"))
    )
    (comp (ref "SW2")
      (value "RUN")
      (fields
        (field (name "Manufacturer Part") "TS-1185EC-C-D-B")
        (field (name "Manufacturer") "XKB Connection(中国星坤)")
      )
      (libsource (lib "") (part "TS-1185EC-C-D-B"))
    )
    (comp (ref "SW3")
      (value "EC11L1525G01")
      (fields (field (name "Manufacturer") "ALPSALPINE(阿尔卑斯阿尔派)"))
      (libsource (lib "") (part "EC11L1525G01"))
    )
    (comp (ref "SW4")
      (value "Prog")
      (fields
        (field (name "Manufacturer Part") "TS-1185EC-C-D-B")
        (field (name "Manufacturer") "XKB Connection(中国星坤)")
      )
      (libsource (lib "") (part "TS-1185EC-C-D-B"))
    )
    (comp (ref "U1") (value "5V") (libsource (lib "") (part "Through hole")))
    (comp (ref "U2")
      (value "1N4148WS")
      (fields (field (name "Manufacturer") "Zhengxin(正芯)"))
      (libsource (lib "") (part "1N4148WS"))
    )
    (comp (ref "U3")
      (value "5V")
      (fields (field (name "Manufacturer Part") "2P,间距5.08mm,弹片压线升降式"))
      (libsource (lib "") (part "2P,间距5.08MM,弹片压线升降式_1"))
    )
    (comp (ref "U4")
      (value "KNX_OUT")
      (fields (field (name "Manufacturer Part") "2P,间距5.08mm,弹片压线升降式"))
      (libsource (lib "") (part "2P,间距5.08MM,弹片压线升降式"))
    )
    (comp (ref "U5")
      (value "KNX_IN")
      (fields (field (name "Manufacturer Part") "2P,间距5.08mm,弹片压线升降式"))
      (libsource (lib "") (part "2P,间距5.08MM,弹片压线升降式_1"))
    )
    (comp (ref "U6")
      (value "TS R1-2433")
      (fields (field (name "Manufacturer") "TRACO POWER"))
      (libsource (lib "") (part "TS R1-2433"))
    )
    (comp (ref "U7") (value "3.3V") (libsource (lib "") (part "Through hole")))
    (comp (ref "U8")
      (value "1N4148WS")
      (fields (field (name "Manufacturer") "Zhengxin(正芯)"))
      (libsource (lib "") (part "1N4148WS"))
    )
    (comp (ref "U9")
      (value "STKNXTR")
      (fields (field (name "Manufacturer") "ST(意法半导体)"))
      (libsource (lib "") (part "STKNXTR"))
    )
    (comp (ref "U10")
      (value "1N4148WS")
      (fields (field (name "Manufacturer") "Zhengxin(正芯)"))
      (libsource (lib "") (part "1N4148WS_1"))
    )
    (comp (ref "U11")
      (value "68Ω(2W)")
      (fields
        (field (name "Manufacturer Part") "HoJLR2512-3W-3.5mR-1%")
        (field (name "Manufacturer") "Milliohm(毫欧)")
      )
      (libsource (lib "") (part "HOJLR2512-3W-3.5MR-1%"))
    )
    (comp (ref "U12") (value "KNX_VCC") (libsource (lib "") (part "Through hole")))
    (comp (ref "U13") (value "KNX_OK") (libsource (lib "") (part "Through hole")))
    (comp (ref "U14") (value "5V") (libsource (lib "") (part "Through hole")))
    (comp (ref "U15") (value "3.3V") (libsource (lib "") (part "Through hole")))
    (comp (ref "U16")
      (value "W25Q128JVSIM")
      (fields (field (name "Manufacturer") "WINBOND(华邦)"))
      (libsource (lib "") (part "W25Q128JVSIM"))
    )
    (comp (ref "U17")
      (value "T0")
      (fields
        (field (name "Manufacturer Part") "DB127V-5.08-3P-GN-S")
        (field (name "Manufacturer") "DIBO(地博电气)")
      )
      (libsource (lib "") (part "DB127V-5.08-3P-GN-S"))
    )
    (comp (ref "U18")
      (value "RP2040")
      (fields (field (name "Manufacturer") "Raspberry Pi(树莓派)"))
      (libsource (lib "") (part "RP2040"))
    )
    (comp (ref "U19")
      (value "T1")
      (fields
        (field (name "Manufacturer Part") "DB127V-5.08-3P-GN-S")
        (field (name "Manufacturer") "DIBO(地博电气)")
      )
      (libsource (lib "") (part "DB127V-5.08-3P-GN-S"))
    )
    (comp (ref "U20") (value "KNX_Rx") (libsource (lib "") (part "Through hole")))
    (comp (ref "U21") (value "KNX_Tx") (libsource (lib "") (part "Through hole")))
    (comp (ref "U22")
      (value "T2")
      (fields
        (field (name "Manufacturer Part") "DB127V-5.08-3P-GN-S")
        (field (name "Manufacturer") "DIBO(地博电气)")
      )
      (libsource (lib "") (part "DB127V-5.08-3P-GN-S"))
    )
    (comp (ref "U23")
      (value "INA219AID")
      (fields (field (name "Manufacturer") "TI(德州仪器)"))
      (libsource (lib "") (part "INA219AID"))
    )
    (comp (ref "U24")
      (value "T3")
      (fields
        (field (name "Manufacturer Part") "DB127V-5.08-3P-GN-S")
        (field (name "Manufacturer") "DIBO(地博电气)")
      )
      (libsource (lib "") (part "DB127V-5.08-3P-GN-S"))
    )
    (comp (ref "U25")
      (value "ATTINY3216")
      (fields
        (field (name "Manufacturer Part") "ATTINY1616-SN")
        (field (name "Manufacturer") "MICROCHIP(美国微芯)")
      )
      (libsource (lib "") (part "ATTINY1616-SN_C614136"))
    )
    (comp (ref "U26") (value "T_Tx") (libsource (lib "") (part "Through hole")))
    (comp (ref "U27")
      (value "T4")
      (fields
        (field (name "Manufacturer Part") "DB127V-5.08-3P-GN-S")
        (field (name "Manufacturer") "DIBO(地博电气)")
      )
      (libsource (lib "") (part "DB127V-5.08-3P-GN-S"))
    )
    (comp (ref "U28") (value "T_Rx") (libsource (lib "") (part "Through hole")))
    (comp (ref "U29")
      (value "PCF8574T/TR")
      (fields (field (name "Manufacturer") "HGSEMI(华冠)"))
      (libsource (lib "") (part "PCF8574T/TR"))
    )
    (comp (ref "U30")
      (value "T5")
      (fields
        (field (name "Manufacturer Part") "DB127V-5.08-3P-GN-S")
        (field (name "Manufacturer") "DIBO(地博电气)")
      )
      (libsource (lib "") (part "DB127V-5.08-3P-GN-S"))
    )
    (comp (ref "U31")
      (value "T6")
      (fields
        (field (name "Manufacturer Part") "DB127V-5.08-3P-GN-S")
        (field (name "Manufacturer") "DIBO(地博电气)")
      )
      (libsource (lib "") (part "DB127V-5.08-3P-GN-S"))
    )
    (comp (ref "U32")
      (value "T7")
      (fields
        (field (name "Manufacturer Part") "DB127V-5.08-3P-GN-S")
        (field (name "Manufacturer") "DIBO(地博电气)")
      )
      (libsource (lib "") (part "DB127V-5.08-3P-GN-S"))
    )
    (comp (ref "U33")
      (value "T8")
      (fields
        (field (name "Manufacturer Part") "DB127V-5.08-3P-GN-S")
        (field (name "Manufacturer") "DIBO(地博电气)")
      )
      (libsource (lib "") (part "DB127V-5.08-3P-GN-S"))
    )
    (comp (ref "U34")
      (value "TB6612FNG,C,8,EL")
      (fields (field (name "Manufacturer") "TOSHIBA(东芝)"))
      (libsource (lib "") (part "TB6612FNG,C,8,EL"))
    )
    (comp (ref "U35")
      (value "TB6612FNG,C,8,EL")
      (fields (field (name "Manufacturer") "TOSHIBA(东芝)"))
      (libsource (lib "") (part "TB6612FNG,C,8,EL"))
    )
    (comp (ref "U36")
      (value "TB6612FNG,C,8,EL")
      (fields (field (name "Manufacturer") "TOSHIBA(东芝)"))
      (libsource (lib "") (part "TB6612FNG,C,8,EL"))
    )
    (comp (ref "U37")
      (value "TB6612FNG,C,8,EL")
      (fields (field (name "Manufacturer") "TOSHIBA(东芝)"))
      (libsource (lib "") (part "TB6612FNG,C,8,EL"))
    )
    (comp (ref "U38")
      (value "M1")
      (fields (field (name "Manufacturer Part") "2P,间距5.08mm,弹片压线升降式"))
      (libsource (lib "") (part "2P,间距5.08MM,弹片压线升降式"))
    )
    (comp (ref "U39")
      (value "M2")
      (fields (field (name "Manufacturer Part") "2P,间距5.08mm,弹片压线升降式"))
      (libsource (lib "") (part "2P,间距5.08MM,弹片压线升降式"))
    )
    (comp (ref "U40")
      (value "M3")
      (fields (field (name "Manufacturer Part") "2P,间距5.08mm,弹片压线升降式"))
      (libsource (lib "") (part "2P,间距5.08MM,弹片压线升降式"))
    )
    (comp (ref "U41")
      (value "M4")
      (fields (field (name "Manufacturer Part") "2P,间距5.08mm,弹片压线升降式"))
      (libsource (lib "") (part "2P,间距5.08MM,弹片压线升降式"))
    )
    (comp (ref "U42")
      (value "M5")
      (fields (field (name "Manufacturer Part") "2P,间距5.08mm,弹片压线升降式"))
      (libsource (lib "") (part "2P,间距5.08MM,弹片压线升降式"))
    )
    (comp (ref "U43")
      (value "M6")
      (fields (field (name "Manufacturer Part") "2P,间距5.08mm,弹片压线升降式"))
      (libsource (lib "") (part "2P,间距5.08MM,弹片压线升降式"))
    )
    (comp (ref "U44")
      (value "M7")
      (fields (field (name "Manufacturer Part") "2P,间距5.08mm,弹片压线升降式"))
      (libsource (lib "") (part "2P,间距5.08MM,弹片压线升降式"))
    )
    (comp (ref "U45")
      (value "M8")
      (fields (field (name "Manufacturer Part") "2P,间距5.08mm,弹片压线升降式"))
      (libsource (lib "") (part "2P,间距5.08MM,弹片压线升降式"))
    )
    (comp (ref "USB1")
      (value "TYPE-C 16PIN 2MD(073)")
      (fields (field (name "Manufacturer") "SHOU HAN(首韩)"))
      (libsource (lib "") (part "TYPE-C 16PIN 2MD(073)"))
    )
    (comp (ref "X1")
      (value "12MHz")
      (fields (field (name "Manufacturer Part") "TAXM12M2QLFCDT1T") (field (name "Manufacturer") "YJX(雅晶鑫)"))
      (libsource (lib "") (part "SMD-5032_2P 12M 20pf 30ppm"))
    )
  )
  (nets
    (net (code "1") (name "1V1") (class "Default")
      (node (ref "C13") (pin "1") (pinfunction "1_1") (pintype "unspecified"))
      (node (ref "C14") (pin "1") (pinfunction "1_1") (pintype "unspecified"))
      (node (ref "C23") (pin "2") (pinfunction "2_2") (pintype "input"))
      (node (ref "U18") (pin "23") (pinfunction "DVDD_23") (pintype "bidirectional"))
      (node (ref "U18") (pin "45") (pinfunction "VREG_VOUT_45") (pintype "bidirectional"))
      (node (ref "U18") (pin "50") (pinfunction "DVDD_50") (pintype "bidirectional"))
    )
    (net (code "2") (name "3.3V") (class "Default")
      (node (ref "C15") (pin "1") (pinfunction "1_1") (pintype "unspecified"))
      (node (ref "C16") (pin "1") (pinfunction "1_1") (pintype "unspecified"))
      (node (ref "C17") (pin "1") (pinfunction "1_1") (pintype "unspecified"))
      (node (ref "C18") (pin "1") (pinfunction "1_1") (pintype "unspecified"))
      (node (ref "C19") (pin "1") (pinfunction "1_1") (pintype "unspecified"))
      (node (ref "C20") (pin "1") (pinfunction "1_1") (pintype "unspecified"))
      (node (ref "C21") (pin "1") (pinfunction "1_1") (pintype "unspecified"))
      (node (ref "C24") (pin "1") (pinfunction "1_1") (pintype "input"))
      (node (ref "C25") (pin "2") (pinfunction "2_2") (pintype "unspecified"))
      (node (ref "C31") (pin "2") (pinfunction "2_2") (pintype "input"))
      (node (ref "C32") (pin "2") (pinfunction "2_2") (pintype "unspecified"))
      (node (ref "C33") (pin "2") (pinfunction "2_2") (pintype "unspecified"))
      (node (ref "C34") (pin "1") (pinfunction "1_1") (pintype "unspecified"))
      (node (ref "C35") (pin "2") (pinfunction "2_2") (pintype "unspecified"))
      (node (ref "C44") (pin "1") (pinfunction "1_1") (pintype "input"))
      (node (ref "C45") (pin "1") (pinfunction "1_1") (pintype "input"))
      (node (ref "C46") (pin "1") (pinfunction "1_1") (pintype "unspecified"))
      (node (ref "C47") (pin "1") (pinfunction "1_1") (pintype "input"))
      (node (ref "C48") (pin "1") (pinfunction "1_1") (pintype "input"))
      (node (ref "C49") (pin "1") (pinfunction "1_1") (pintype "unspecified"))
      (node (ref "C50") (pin "1") (pinfunction "1_1") (pintype "unspecified"))
      (node (ref "C51") (pin "1") (pinfunction "1_1") (pintype "unspecified"))
      (node (ref "D5") (pin "1") (pinfunction "K_1") (pintype "unspecified"))
      (node (ref "LCD1") (pin "15") (pinfunction "BLA_15") (pintype "unspecified"))
      (node (ref "LCD1") (pin "2") (pinfunction "VDD_2") (pintype "unspecified"))
      (node (ref "R10") (pin "2") (pinfunction "2_2") (pintype "input"))
      (node (ref "R17") (pin "2") (pinfunction "2_2") (pintype "input"))
      (node (ref "R19") (pin "1") (pinfunction "1_1") (pintype "input"))
      (node (ref "R20") (pin "2") (pinfunction "2_2") (pintype "input"))
      (node (ref "R22") (pin "2") (pinfunction "2_2") (pintype "input"))
      (node (ref "R23") (pin "2") (pinfunction "2_2") (pintype "input"))
      (node (ref "R24") (pin "2") (pinfunction "2_2") (pintype "input"))
      (node (ref "R25") (pin "2") (pinfunction "2_2") (pintype "input"))
      (node (ref "R26") (pin "1") (pinfunction "1_1") (pintype "input"))
      (node (ref "R27") (pin "1") (pinfunction "1_1") (pintype "input"))
      (node (ref "R28") (pin "2") (pinfunction "2_2") (pintype "input"))
      (node (ref "R29") (pin "1") (pinfunction "1_1") (pintype "unspecified"))
      (node (ref "R30") (pin "2") (pinfunction "2_2") (pintype "input"))
      (node (ref "R31") (pin "2") (pinfunction "2_2") (pintype "input"))
      (node (ref "R33") (pin "1") (pinfunction "1_1") (pintype "input"))
      (node (ref "R35") (pin "2") (pinfunction "2_2") (pintype "input"))
      (node (ref "R36") (pin "2") (pinfunction "2_2") (pintype "input"))
      (node (ref "R37") (pin "2") (pinfunction "2_2") (pintype "input"))
      (node (ref "R38") (pin "2") (pinfunction "2_2") (pintype "input"))
      (node (ref "R42") (pin "2") (pinfunction "2_2") (pintype "input"))
      (node (ref "R44") (pin "2") (pinfunction "2_2") (pintype "input"))
      (node (ref "R49") (pin "2") (pinfunction "2_2") (pintype "input"))
      (node (ref "R50") (pin "2") (pinfunction "2_2") (pintype "input"))
      (node (ref "R56") (pin "2") (pinfunction "2_2") (pintype "input"))
      (node (ref "R57") (pin "2") (pinfunction "2_2") (pintype "input"))
      (node (ref "R6") (pin "1") (pinfunction "1_1") (pintype "input"))
      (node (ref "R8") (pin "1") (pinfunction "1_1") (pintype "input"))
      (node (ref "U15") (pin "1") (pinfunction "1_1") (pintype "unspecified"))
      (node (ref "U16") (pin "8") (pinfunction "VCC_8") (pintype "unspecified"))
      (node (ref "U17") (pin "3") (pinfunction "3_3") (pintype "unspecified"))
      (node (ref "U18") (pin "1") (pinfunction "IOVDD_1") (pintype "bidirectional"))
      (node (ref "U18") (pin "10") (pinfunction "IOVDD_10") (pintype "bidirectional"))
      (node (ref "U18") (pin "22") (pinfunction "IOVDD_22") (pintype "bidirectional"))
      (node (ref "U18") (pin "33") (pinfunction "IOVDD_33") (pintype "bidirectional"))
      (node (ref "U18") (pin "42") (pinfunction "IOVDD_42") (pintype "bidirectional"))
      (node (ref "U18") (pin "43") (pinfunction "ADC_AVDD_43") (pintype "bidirectional"))
      (node (ref "U18") (pin "44") (pinfunction "VREG_IN_44") (pintype "bidirectional"))
      (node (ref "U18") (pin "48") (pinfunction "USB_VDD_48") (pintype "bidirectional"))
      (node (ref "U18") (pin "49") (pinfunction "IOVDD_49") (pintype "bidirectional"))
      (node (ref "U19") (pin "3") (pinfunction "3_3") (pintype "unspecified"))
      (node (ref "U22") (pin "3") (pinfunction "3_3") (pintype "unspecified"))
      (node (ref "U23") (pin "5") (pinfunction "VS_5") (pintype "unspecified"))
      (node (ref "U24") (pin "3") (pinfunction "3_3") (pintype "unspecified"))
      (node (ref "U25") (pin "1") (pinfunction "VDD_1") (pintype "unspecified"))
      (node (ref "U27") (pin "3") (pinfunction "3_3") (pintype "unspecified"))
      (node (ref "U29") (pin "1") (pinfunction "A0_1") (pintype "unspecified"))
      (node (ref "U29") (pin "16") (pinfunction "VDD_16") (pintype "unspecified"))
      (node (ref "U29") (pin "2") (pinfunction "A1_2") (pintype "unspecified"))
      (node (ref "U29") (pin "3") (pinfunction "A2_3") (pintype "unspecified"))
      (node (ref "U30") (pin "3") (pinfunction "3_3") (pintype "unspecified"))
      (node (ref "U31") (pin "3") (pinfunction "3_3") (pintype "unspecified"))
      (node (ref "U32") (pin "3") (pinfunction "3_3") (pintype "unspecified"))
      (node (ref "U33") (pin "3") (pinfunction "3_3") (pintype "unspecified"))
      (node (ref "U34") (pin "19") (pinfunction "STBY_19") (pintype "unspecified"))
      (node (ref "U34") (pin "20") (pinfunction "VCC_20") (pintype "unspecified"))
      (node (ref "U35") (pin "19") (pinfunction "STBY_19") (pintype "unspecified"))
      (node (ref "U35") (pin "20") (pinfunction "VCC_20") (pintype "unspecified"))
      (node (ref "U36") (pin "19") (pinfunction "STBY_19") (pintype "unspecified"))
      (node (ref "U36") (pin "20") (pinfunction "VCC_20") (pintype "unspecified"))
      (node (ref "U37") (pin "19") (pinfunction "STBY_19") (pintype "unspecified"))
      (node (ref "U37") (pin "20") (pinfunction "VCC_20") (pintype "unspecified"))
      (node (ref "U6") (pin "3") (pinfunction "+Vout_3") (pintype "unspecified"))
      (node (ref "U7") (pin "1") (pinfunction "1_1") (pintype "unspecified"))
    )
    (net (code "3") (name "5V") (class "Default")
      (node (ref "CN1") (pin "1") (pinfunction "1_1") (pintype "unspecified"))
      (node (ref "D1") (pin "2") (pinfunction "A_2") (pintype "unspecified"))
      (node (ref "D3") (pin "1") (pinfunction "K_1") (pintype "unspecified"))
      (node (ref "D4") (pin "1") (pinfunction "C_1") (pintype "unspecified"))
      (node (ref "F1") (pin "2") (pinfunction "2_2") (pintype "unspecified"))
      (node (ref "R7") (pin "2") (pinfunction "2_2") (pintype "input"))
      (node (ref "U1") (pin "1") (pinfunction "1_1") (pintype "unspecified"))
      (node (ref "U14") (pin "1") (pinfunction "1_1") (pintype "unspecified"))
    )
    (net (code "4") (name "5V_") (class "Default")
      (node (ref "D6") (pin "1") (pinfunction "K_1") (pintype "unspecified"))
      (node (ref "F1") (pin "1") (pinfunction "1_1") (pintype "unspecified"))
      (node (ref "Q1") (pin "2") (pinfunction "S_2") (pintype "unspecified"))
      (node (ref "U3") (pin "1") (pinfunction "1_1") (pintype "unspecified"))
    )
    (net (code "5") (name "A") (class "Default")
      (node (ref "C27") (pin "2") (pinfunction "2_2") (pintype "input"))
      (node (ref "R26") (pin "2") (pinfunction "2_2") (pintype "input"))
      (node (ref "SW3") (pin "A") (pinfunction "A_A") (pintype "unspecified"))
      (node (ref "U18") (pin "8") (pinfunction "GPIO6_8") (pintype "bidirectional"))
    )
    (net (code "6") (name "B") (class "Default")
      (node (ref "C28") (pin "2") (pinfunction "2_2") (pintype "input"))
      (node (ref "R27") (pin "2") (pinfunction "2_2") (pintype "input"))
      (node (ref "SW3") (pin "B") (pinfunction "B_B") (pintype "unspecified"))
      (node (ref "U18") (pin "9") (pinfunction "GPIO7_9") (pintype "bidirectional"))
    )
    (net (code "7") (name "Button") (class "Default")
      (node (ref "C26") (pin "1") (pinfunction "1_1") (pintype "unspecified"))
      (node (ref "R19") (pin "2") (pinfunction "2_2") (pintype "input"))
      (node (ref "R21") (pin "1") (pinfunction "1_1") (pintype "input"))
      (node (ref "U18") (pin "4") (pinfunction "GPIO2_4") (pintype "bidirectional"))
    )
    (net (code "8") (name "CPH") (class "Default")
      (node (ref "R13") (pin "1") (pinfunction "1_1") (pintype "input"))
      (node (ref "U9") (pin "5") (pinfunction "CP_H_5") (pintype "unspecified"))
    )
    (net (code "9") (name "CPL") (class "Default")
      (node (ref "R11") (pin "1") (pinfunction "1_1") (pintype "input"))
      (node (ref "U9") (pin "6") (pinfunction "CP_L_6") (pintype "unspecified"))
    )
    (net (code "10") (name "CS") (class "Default")
      (node (ref "R23") (pin "1") (pinfunction "1_1") (pintype "input"))
      (node (ref "U18") (pin "32") (pinfunction "GPIO21_32") (pintype "bidirectional"))
      (node (ref "U25") (pin "2") (pinfunction "PA4_2") (pintype "unspecified"))
    )
    (net (code "11") (name "D+") (class "Default")
      (node (ref "R16") (pin "1") (pinfunction "1_1") (pintype "input"))
      (node (ref "USB1") (pin "6") (pinfunction "DP1_6") (pintype "unspecified"))
      (node (ref "USB1") (pin "8") (pinfunction "DP2_8") (pintype "unspecified"))
    )
    (net (code "12") (name "D-") (class "Default")
      (node (ref "R18") (pin "1") (pinfunction "1_1") (pintype "input"))
      (node (ref "USB1") (pin "5") (pinfunction "DN2_5") (pintype "unspecified"))
      (node (ref "USB1") (pin "7") (pinfunction "DN1_7") (pintype "unspecified"))
    )
    (net (code "13") (name "DCDC_FB") (class "Default")
      (node (ref "C11") (pin "2") (pinfunction "2_2") (pintype "input"))
      (node (ref "R14") (pin "1") (pinfunction "1_1") (pintype "input"))
      (node (ref "R15") (pin "2") (pinfunction "2_2") (pintype "input"))
      (node (ref "U9") (pin "18") (pinfunction "DCDC_FB_18") (pintype "unspecified"))
    )
    (net (code "14") (name "DCDC_LX") (class "Default")
      (node (ref "L1") (pin "1") (pinfunction "1_1") (pintype "unspecified"))
      (node (ref "U9") (pin "15") (pinfunction "DCDC_LX_15") (pintype "unspecified"))
    )
    (net (code "15") (name "DCDC_SS") (class "Default")
      (node (ref "C2") (pin "1") (pinfunction "1_1") (pintype "unspecified"))
      (node (ref "U9") (pin "17") (pinfunction "DCDC_SS_17") (pintype "unspecified"))
    )
    (net (code "16") (name "GND") (class "Default")
      (node (ref "C1") (pin "1") (pinfunction "1_1") (pintype "input"))
      (node (ref "C12") (pin "2") (pinfunction "2_2") (pintype "input"))
      (node (ref "C13") (pin "2") (pinfunction "2_2") (pintype "unspecified"))
      (node (ref "C14") (pin "2") (pinfunction "2_2") (pintype "unspecified"))
      (node (ref "C15") (pin "2") (pinfunction "2_2") (pintype "unspecified"))
      (node (ref "C16") (pin "2") (pinfunction "2_2") (pintype "unspecified"))
      (node (ref "C17") (pin "2") (pinfunction "2_2") (pintype "unspecified"))
      (node (ref "C18") (pin "2") (pinfunction "2_2") (pintype "unspecified"))
      (node (ref "C19") (pin "2") (pinfunction "2_2") (pintype "unspecified"))
      (node (ref "C2") (pin "2") (pinfunction "2_2") (pintype "unspecified"))
      (node (ref "C20") (pin "2") (pinfunction "2_2") (pintype "unspecified"))
      (node (ref "C21") (pin "2") (pinfunction "2_2") (pintype "unspecified"))
      (node (ref "C22") (pin "2") (pinfunction "2_2") (pintype "input"))
      (node (ref "C23") (pin "1") (pinfunction "1_1") (pintype "input"))
      (node (ref "C24") (pin "2") (pinfunction "2_2") (pintype "input"))
      (node (ref "C25") (pin "1") (pinfunction "1_1") (pintype "unspecified"))
      (node (ref "C26") (pin "2") (pinfunction "2_2") (pintype "unspecified"))
      (node (ref "C27") (pin "1") (pinfunction "1_1") (pintype "input"))
      (node (ref "C28") (pin "1") (pinfunction "1_1") (pintype "input"))
      (node (ref "C29") (pin "1") (pinfunction "1_1") (pintype "input"))
      (node (ref "C3") (pin "1") (pinfunction "1_1") (pintype "input"))
      (node (ref "C30") (pin "1") (pinfunction "1_1") (pintype "input"))
      (node (ref "C32") (pin "1") (pinfunction "1_1") (pintype "unspecified"))
      (node (ref "C33") (pin "1") (pinfunction "1_1") (pintype "unspecified"))
      (node (ref "C34") (pin "2") (pinfunction "2_2") (pintype "unspecified"))
      (node (ref "C35") (pin "1") (pinfunction "1_1") (pintype "unspecified"))
      (node (ref "C36") (pin "1") (pinfunction "1_1") (pintype "unspecified"))
      (node (ref "C37") (pin "1") (pinfunction "1_1") (pintype "unspecified"))
      (node (ref "C38") (pin "1") (pinfunction "1_1") (pintype "input"))
      (node (ref "C39") (pin "1") (pinfunction "1_1") (pintype "unspecified"))
      (node (ref "C40") (pin "1") (pinfunction "1_1") (pintype "unspecified"))
      (node (ref "C41") (pin "1") (pinfunction "1_1") (pintype "input"))
      (node (ref "C42") (pin "1") (pinfunction "1_1") (pintype "input"))
      (node (ref "C43") (pin "1") (pinfunction "1_1") (pintype "input"))
      (node (ref "C44") (pin "2") (pinfunction "2_2") (pintype "input"))
      (node (ref "C45") (pin "2") (pinfunction "2_2") (pintype "input"))
      (node (ref "C46") (pin "2") (pinfunction "2_2") (pintype "unspecified"))
      (node (ref "C47") (pin "2") (pinfunction "2_2") (pintype "input"))
      (node (ref "C48") (pin "2") (pinfunction "2_2") (pintype "input"))
      (node (ref "C49") (pin "2") (pinfunction "2_2") (pintype "unspecified"))
      (node (ref "C50") (pin "2") (pinfunction "2_2") (pintype "unspecified"))
      (node (ref "C51") (pin "2") (pinfunction "2_2") (pintype "unspecified"))
      (node (ref "C7") (pin "1") (pinfunction "1_1") (pintype "input"))
      (node (ref "C8") (pin "2") (pinfunction "2_2") (pintype "unspecified"))
      (node (ref "C9") (pin "2") (pinfunction "2_2") (pintype "unspecified"))
      (node (ref "CN1") (pin "5") (pinfunction "5_5") (pintype "unspecified"))
      (node (ref "CN1") (pin "6") (pinfunction "6_6") (pintype "unspecified"))
      (node (ref "D2") (pin "2") (pinfunction "2_2") (pintype "unspecified"))
      (node (ref "D3") (pin "2") (pinfunction "A_2") (pintype "unspecified"))
      (node (ref "D4") (pin "2") (pinfunction "A_2") (pintype "unspecified"))
      (node (ref "D5") (pin "2") (pinfunction "A_2") (pintype "unspecified"))
      (node (ref "LCD1") (pin "1") (pinfunction "VSS_1") (pintype "unspecified"))
      (node (ref "LCD1") (pin "10") (pinfunction "DB3_10") (pintype "unspecified"))
      (node (ref "LCD1") (pin "7") (pinfunction "DB0_7") (pintype "unspecified"))
      (node (ref "LCD1") (pin "8") (pinfunction "DB1_8") (pintype "unspecified"))
      (node (ref "LCD1") (pin "9") (pinfunction "DB2_9") (pintype "unspecified"))
      (node (ref "LED1") (pin "2") (pinfunction "-_2") (pintype "unspecified"))
      (node (ref "LED10") (pin "2") (pinfunction "-_2") (pintype "unspecified"))
      (node (ref "LED11") (pin "2") (pinfunction "-_2") (pintype "unspecified"))
      (node (ref "LED12") (pin "2") (pinfunction "-_2") (pintype "unspecified"))
      (node (ref "LED13") (pin "2") (pinfunction "-_2") (pintype "unspecified"))
      (node (ref "LED14") (pin "2") (pinfunction "-_2") (pintype "unspecified"))
      (node (ref "LED15") (pin "2") (pinfunction "-_2") (pintype "unspecified"))
      (node (ref "LED16") (pin "2") (pinfunction "-_2") (pintype "unspecified"))
      (node (ref "LED2") (pin "2") (pinfunction "-_2") (pintype "unspecified"))
      (node (ref "LED3") (pin "2") (pinfunction "-_2") (pintype "unspecified"))
      (node (ref "LED4") (pin "2") (pinfunction "-_2") (pintype "unspecified"))
      (node (ref "LED5") (pin "2") (pinfunction "-_2") (pintype "unspecified"))
      (node (ref "LED6") (pin "2") (pinfunction "-_2") (pintype "unspecified"))
      (node (ref "LED7") (pin "2") (pinfunction "-_2") (pintype "unspecified"))
      (node (ref "LED8") (pin "2") (pinfunction "-_2") (pintype "unspecified"))
      (node (ref "LED9") (pin "2") (pinfunction "-_2") (pintype "unspecified"))
      (node (ref "Q2") (pin "2") (pinfunction "2_2") (pintype "input"))
      (node (ref "R1") (pin "1") (pinfunction "1_1") (pintype "input"))
      (node (ref "R15") (pin "1") (pinfunction "1_1") (pintype "input"))
      (node (ref "R2") (pin "2") (pinfunction "2_2") (pintype "input"))
      (node (ref "R3") (pin "1") (pinfunction "1_1") (pintype "input"))
      (node (ref "R5") (pin "2") (pinfunction "2_2") (pintype "input"))
      (node (ref "R55") (pin "2") (pinfunction "2_2") (pintype "unspecified"))
      (node (ref "R9") (pin "1") (pinfunction "1_1") (pintype "input"))
      (node (ref "S1") (pin "2") (pinfunction "2_2") (pintype "unspecified"))
      (node (ref "SW1") (pin "2") (pinfunction "2_2") (pintype "unspecified"))
      (node (ref "SW2") (pin "2") (pinfunction "2_2") (pintype "unspecified"))
      (node (ref "SW3") (pin "C") (pinfunction "C_C") (pintype "unspecified"))
      (node (ref "SW3") (pin "E") (pinfunction "E_E") (pintype "unspecified"))
      (node (ref "SW4") (pin "2") (pinfunction "2_2") (pintype "unspecified"))
      (node (ref "U16") (pin "4") (pinfunction "GND_4") (pintype "unspecified"))
      (node (ref "U17") (pin "1") (pinfunction "1_1") (pintype "unspecified"))
      (node (ref "U18") (pin "19") (pinfunction "TESTEN_19") (pintype "unspecified"))
      (node (ref "U18") (pin "57") (pinfunction "GND_57") (pintype "bidirectional"))
      (node (ref "U19") (pin "1") (pinfunction "1_1") (pintype "unspecified"))
      (node (ref "U22") (pin "1") (pinfunction "1_1") (pintype "unspecified"))
      (node (ref "U23") (pin "1") (pinfunction "A1_1") (pintype "unspecified"))
      (node (ref "U23") (pin "2") (pinfunction "A0_2") (pintype "unspecified"))
      (node (ref "U23") (pin "6") (pinfunction "GND_6") (pintype "unspecified"))
      (node (ref "U24") (pin "1") (pinfunction "1_1") (pintype "unspecified"))
      (node (ref "U25") (pin "20") (pinfunction "GND_20") (pintype "unspecified"))
      (node (ref "U27") (pin "1") (pinfunction "1_1") (pintype "unspecified"))
      (node (ref "U29") (pin "8") (pinfunction "VSS_8") (pintype "unspecified"))
      (node (ref "U3") (pin "2") (pinfunction "2_2") (pintype "unspecified"))
      (node (ref "U30") (pin "1") (pinfunction "1_1") (pintype "unspecified"))
      (node (ref "U31") (pin "1") (pinfunction "1_1") (pintype "unspecified"))
      (node (ref "U32") (pin "1") (pinfunction "1_1") (pintype "unspecified"))
      (node (ref "U33") (pin "1") (pinfunction "1_1") (pintype "unspecified"))
      (node (ref "U34") (pin "10") (pinfunction "PGND2_10") (pintype "unspecified"))
      (node (ref "U34") (pin "18") (pinfunction "GND_18") (pintype "unspecified"))
      (node (ref "U34") (pin "3") (pinfunction "PGND1_3") (pintype "unspecified"))
      (node (ref "U34") (pin "4") (pinfunction "PGND1_4") (pintype "unspecified"))
      (node (ref "U34") (pin "9") (pinfunction "PGND2_9") (pintype "unspecified"))
      (node (ref "U35") (pin "10") (pinfunction "PGND2_10") (pintype "unspecified"))
      (node (ref "U35") (pin "18") (pinfunction "GND_18") (pintype "unspecified"))
      (node (ref "U35") (pin "3") (pinfunction "PGND1_3") (pintype "unspecified"))
      (node (ref "U35") (pin "4") (pinfunction "PGND1_4") (pintype "unspecified"))
      (node (ref "U35") (pin "9") (pinfunction "PGND2_9") (pintype "unspecified"))
      (node (ref "U36") (pin "10") (pinfunction "PGND2_10") (pintype "unspecified"))
      (node (ref "U36") (pin "18") (pinfunction "GND_18") (pintype "unspecified"))
      (node (ref "U36") (pin "3") (pinfunction "PGND1_3") (pintype "unspecified"))
      (node (ref "U36") (pin "4") (pinfunction "PGND1_4") (pintype "unspecified"))
      (node (ref "U36") (pin "9") (pinfunction "PGND2_9") (pintype "unspecified"))
      (node (ref "U37") (pin "10") (pinfunction "PGND2_10") (pintype "unspecified"))
      (node (ref "U37") (pin "18") (pinfunction "GND_18") (pintype "unspecified"))
      (node (ref "U37") (pin "3") (pinfunction "PGND1_3") (pintype "unspecified"))
      (node (ref "U37") (pin "4") (pinfunction "PGND1_4") (pintype "unspecified"))
      (node (ref "U37") (pin "9") (pinfunction "PGND2_9") (pintype "unspecified"))
      (node (ref "U4") (pin "2") (pinfunction "2_2") (pintype "unspecified"))
      (node (ref "U5") (pin "2") (pinfunction "2_2") (pintype "unspecified"))
      (node (ref "U6") (pin "2") (pinfunction "GND_2") (pintype "unspecified"))
      (node (ref "U8") (pin "2") (pinfunction "A_2") (pintype "unspecified"))
      (node (ref "U9") (pin "12") (pinfunction "KNX_B_12") (pintype "unspecified"))
      (node (ref "U9") (pin "16") (pinfunction "DCDC_GND_16") (pintype "unspecified"))
      (node (ref "U9") (pin "22") (pinfunction "VCC_SEL_22") (pintype "unspecified"))
      (node (ref "U9") (pin "25") (pinfunction "EP_25") (pintype "unspecified"))
      (node (ref "U9") (pin "4") (pinfunction "KNX_B_4") (pintype "unspecified"))
      (node (ref "USB1") (pin "1") (pinfunction "GND_1") (pintype "unspecified"))
      (node (ref "USB1") (pin "12") (pinfunction "GND_12") (pintype "unspecified"))
      (node (ref "USB1") (pin "13") (pinfunction "SHELL_13") (pintype "unspecified"))
      (node (ref "USB1") (pin "14") (pinfunction "SHELL_14") (pintype "unspecified"))
    )
    (net (code "17") (name "IN_1") (class "Default")
      (node (ref "R41") (pin "2") (pinfunction "2_2") (pintype "input"))
      (node (ref "U18") (pin "29") (pinfunction "GPIO18_29") (pintype "bidirectional"))
      (node (ref "U34") (pin "17") (pinfunction "BIN1_17") (pintype "unspecified"))
      (node (ref "U34") (pin "21") (pinfunction "AIN1_21") (pintype "unspecified"))
      (node (ref "U35") (pin "17") (pinfunction "BIN1_17") (pintype "unspecified"))
      (node (ref "U35") (pin "21") (pinfunction "AIN1_21") (pintype "unspecified"))
      (node (ref "U36") (pin "17") (pinfunction "BIN1_17") (pintype "unspecified"))
      (node (ref "U36") (pin "21") (pinfunction "AIN1_21") (pintype "unspecified"))
      (node (ref "U37") (pin "17") (pinfunction "BIN1_17") (pintype "unspecified"))
      (node (ref "U37") (pin "21") (pinfunction "AIN1_21") (pintype "unspecified"))
    )
    (net (code "18") (name "IN_2") (class "Default")
      (node (ref "R43") (pin "2") (pinfunction "2_2") (pintype "input"))
      (node (ref "U18") (pin "30") (pinfunction "GPIO19_30") (pintype "bidirectional"))
      (node (ref "U34") (pin "16") (pinfunction "BIN2_16") (pintype "unspecified"))
      (node (ref "U34") (pin "22") (pinfunction "AIN2_22") (pintype "unspecified"))
      (node (ref "U35") (pin "16") (pinfunction "BIN2_16") (pintype "unspecified"))
      (node (ref "U35") (pin "22") (pinfunction "AIN2_22") (pintype "unspecified"))
      (node (ref "U36") (pin "16") (pinfunction "BIN2_16") (pintype "unspecified"))
      (node (ref "U36") (pin "22") (pinfunction "AIN2_22") (pintype "unspecified"))
      (node (ref "U37") (pin "16") (pinfunction "BIN2_16") (pintype "unspecified"))
      (node (ref "U37") (pin "22") (pinfunction "AIN2_22") (pintype "unspecified"))
    )
    (net (code "19") (name "KNC_AC") (class "Default")
      (node (ref "C4") (pin "2") (pinfunction "2_2") (pintype "input"))
      (node (ref "U8") (pin "1") (pinfunction "K_1") (pintype "unspecified"))
      (node (ref "U9") (pin "2") (pinfunction "KNX_AC_2") (pintype "unspecified"))
    )
    (net (code "20") (name "KNX+") (class "Default")
      (node (ref "C10") (pin "2") (pinfunction "2_2") (pintype "unspecified"))
      (node (ref "D2") (pin "1") (pinfunction "1_1") (pintype "unspecified"))
      (node (ref "R2") (pin "1") (pinfunction "1_1") (pintype "input"))
      (node (ref "U2") (pin "2") (pinfunction "A_2") (pintype "unspecified"))
      (node (ref "U4") (pin "1") (pinfunction "1_1") (pintype "unspecified"))
      (node (ref "U5") (pin "1") (pinfunction "1_1") (pintype "unspecified"))
    )
    (net (code "21") (name "KNX_A") (class "Default")
      (node (ref "C4") (pin "1") (pinfunction "1_1") (pintype "input"))
      (node (ref "C6") (pin "1") (pinfunction "1_1") (pintype "input"))
      (node (ref "U11") (pin "2") (pinfunction "2_2") (pintype "unspecified"))
      (node (ref "U2") (pin "1") (pinfunction "K_1") (pintype "unspecified"))
      (node (ref "U9") (pin "11") (pinfunction "KNX_A_11") (pintype "unspecified"))
    )
    (net (code "22") (name "KNX_OK") (class "Default")
      (node (ref "U13") (pin "1") (pinfunction "1_1") (pintype "unspecified"))
      (node (ref "U18") (pin "31") (pinfunction "GPIO20_31") (pintype "bidirectional"))
      (node (ref "U9") (pin "21") (pinfunction "KNX_OK_21") (pintype "unspecified"))
    )
    (net (code "23") (name "KNX_Rx") (class "Default")
      (node (ref "JMP2") (pin "2") (pinfunction "2_2") (pintype "unspecified"))
      (node (ref "R22") (pin "1") (pinfunction "1_1") (pintype "input"))
      (node (ref "U20") (pin "1") (pinfunction "1_1") (pintype "unspecified"))
      (node (ref "U9") (pin "23") (pinfunction "KNX_RX_23") (pintype "unspecified"))
    )
    (net (code "24") (name "KNX_Rx&#039;") (class "Default")
      (node (ref "JMP2") (pin "1") (pinfunction "1_1") (pintype "unspecified"))
      (node (ref "JMP3") (pin "1") (pinfunction "1_1") (pintype "unspecified"))
    )
    (net (code "25") (name "KNX_Rx'") (class "Default")
      (node (ref "U18") (pin "3") (pinfunction "GPIO1_3") (pintype "bidirectional"))
    )
    (net (code "26") (name "KNX_Tx") (class "Default")
      (node (ref "JMP3") (pin "2") (pinfunction "2_2") (pintype "unspecified"))
      (node (ref "R17") (pin "1") (pinfunction "1_1") (pintype "input"))
      (node (ref "U21") (pin "1") (pinfunction "1_1") (pintype "unspecified"))
      (node (ref "U9") (pin "24") (pinfunction "KNX_TX_24") (pintype "unspecified"))
    )
    (net (code "27") (name "KNX_Tx&#039;") (class "Default")
      (node (ref "JMP2") (pin "3") (pinfunction "3_3") (pintype "unspecified"))
      (node (ref "JMP3") (pin "3") (pinfunction "3_3") (pintype "unspecified"))
    )
    (net (code "28") (name "KNX_Tx'") (class "Default")
      (node (ref "U18") (pin "2") (pinfunction "GPIO0_2") (pintype "bidirectional"))
    )
    (net (code "29") (name "KNX_VCC") (class "Default")
      (node (ref "C11") (pin "1") (pinfunction "1_1") (pintype "input"))
      (node (ref "C22") (pin "1") (pinfunction "1_1") (pintype "input"))
      (node (ref "JMP1") (pin "1") (pinfunction "1_1") (pintype "unspecified"))
      (node (ref "L1") (pin "2") (pinfunction "2_2") (pintype "unspecified"))
      (node (ref "R14") (pin "2") (pinfunction "2_2") (pintype "input"))
      (node (ref "U12") (pin "1") (pinfunction "1_1") (pintype "unspecified"))
    )
    (net (code "30") (name "LED") (class "Default")
      (node (ref "R39") (pin "2") (pinfunction "2_2") (pintype "input"))
      (node (ref "U18") (pin "37") (pinfunction "GPIO25_37") (pintype "bidirectional"))
    )
    (net (code "31") (name "LED_2") (class "Default")
      (node (ref "R32") (pin "2") (pinfunction "2_2") (pintype "input"))
      (node (ref "U25") (pin "15") (pinfunction "PC3_15") (pintype "unspecified"))
    )
    (net (code "32") (name "M1+") (class "Default")
      (node (ref "U34") (pin "1") (pinfunction "AO1_1") (pintype "unspecified"))
      (node (ref "U34") (pin "2") (pinfunction "AO1_2") (pintype "unspecified"))
      (node (ref "U38") (pin "1") (pinfunction "1_1") (pintype "unspecified"))
    )
    (net (code "33") (name "M1-") (class "Default")
      (node (ref "U34") (pin "5") (pinfunction "AO2_5") (pintype "unspecified"))
      (node (ref "U34") (pin "6") (pinfunction "AO2_6") (pintype "unspecified"))
      (node (ref "U38") (pin "2") (pinfunction "2_2") (pintype "unspecified"))
    )
    (net (code "34") (name "M1_EN") (class "Default")
      (node (ref "R48") (pin "2") (pinfunction "2_2") (pintype "input"))
      (node (ref "U18") (pin "13") (pinfunction "GPIO10_13") (pintype "bidirectional"))
      (node (ref "U34") (pin "23") (pinfunction "PWMA_23") (pintype "unspecified"))
    )
    (net (code "35") (name "M2+") (class "Default")
      (node (ref "U34") (pin "11") (pinfunction "BO1_11") (pintype "unspecified"))
      (node (ref "U34") (pin "12") (pinfunction "BO1_12") (pintype "unspecified"))
      (node (ref "U39") (pin "1") (pinfunction "1_1") (pintype "unspecified"))
    )
    (net (code "36") (name "M2-") (class "Default")
      (node (ref "U34") (pin "7") (pinfunction "BO2_7") (pintype "unspecified"))
      (node (ref "U34") (pin "8") (pinfunction "BO2_8") (pintype "unspecified"))
      (node (ref "U39") (pin "2") (pinfunction "2_2") (pintype "unspecified"))
    )
    (net (code "37") (name "M2_EN") (class "Default")
      (node (ref "R54") (pin "2") (pinfunction "2_2") (pintype "input"))
      (node (ref "U18") (pin "14") (pinfunction "GPIO11_14") (pintype "bidirectional"))
      (node (ref "U34") (pin "15") (pinfunction "PWMB_15") (pintype "unspecified"))
    )
    (net (code "38") (name "M3+") (class "Default")
      (node (ref "U36") (pin "1") (pinfunction "AO1_1") (pintype "unspecified"))
      (node (ref "U36") (pin "2") (pinfunction "AO1_2") (pintype "unspecified"))
      (node (ref "U40") (pin "1") (pinfunction "1_1") (pintype "unspecified"))
    )
    (net (code "39") (name "M3-") (class "Default")
      (node (ref "U36") (pin "5") (pinfunction "AO2_5") (pintype "unspecified"))
      (node (ref "U36") (pin "6") (pinfunction "AO2_6") (pintype "unspecified"))
      (node (ref "U40") (pin "2") (pinfunction "2_2") (pintype "unspecified"))
    )
    (net (code "40") (name "M3_EN") (class "Default")
      (node (ref "R47") (pin "2") (pinfunction "2_2") (pintype "input"))
      (node (ref "U18") (pin "15") (pinfunction "GPIO12_15") (pintype "bidirectional"))
      (node (ref "U36") (pin "23") (pinfunction "PWMA_23") (pintype "unspecified"))
    )
    (net (code "41") (name "M4+") (class "Default")
      (node (ref "U36") (pin "11") (pinfunction "BO1_11") (pintype "unspecified"))
      (node (ref "U36") (pin "12") (pinfunction "BO1_12") (pintype "unspecified"))
      (node (ref "U41") (pin "1") (pinfunction "1_1") (pintype "unspecified"))
    )
    (net (code "42") (name "M4-") (class "Default")
      (node (ref "U36") (pin "7") (pinfunction "BO2_7") (pintype "unspecified"))
      (node (ref "U36") (pin "8") (pinfunction "BO2_8") (pintype "unspecified"))
      (node (ref "U41") (pin "2") (pinfunction "2_2") (pintype "unspecified"))
    )
    (net (code "43") (name "M4_EN") (class "Default")
      (node (ref "R53") (pin "2") (pinfunction "2_2") (pintype "input"))
      (node (ref "U18") (pin "16") (pinfunction "GPIO13_16") (pintype "bidirectional"))
      (node (ref "U36") (pin "15") (pinfunction "PWMB_15") (pintype "unspecified"))
    )
    (net (code "44") (name "M5+") (class "Default")
      (node (ref "U37") (pin "1") (pinfunction "AO1_1") (pintype "unspecified"))
      (node (ref "U37") (pin "2") (pinfunction "AO1_2") (pintype "unspecified"))
      (node (ref "U42") (pin "1") (pinfunction "1_1") (pintype "unspecified"))
    )
    (net (code "45") (name "M5-") (class "Default")
      (node (ref "U37") (pin "5") (pinfunction "AO2_5") (pintype "unspecified"))
      (node (ref "U37") (pin "6") (pinfunction "AO2_6") (pintype "unspecified"))
      (node (ref "U42") (pin "2") (pinfunction "2_2") (pintype "unspecified"))
    )
    (net (code "46") (name "M5_EN") (class "Default")
      (node (ref "R45") (pin "2") (pinfunction "2_2") (pintype "input"))
      (node (ref "U18") (pin "17") (pinfunction "GPIO14_17") (pintype "bidirectional"))
      (node (ref "U37") (pin "23") (pinfunction "PWMA_23") (pintype "unspecified"))
    )
    (net (code "47") (name "M6+") (class "Default")
      (node (ref "U37") (pin "11") (pinfunction "BO1_11") (pintype "unspecified"))
      (node (ref "U37") (pin "12") (pinfunction "BO1_12") (pintype "unspecified"))
      (node (ref "U43") (pin "1") (pinfunction "1_1") (pintype "unspecified"))
    )
    (net (code "48") (name "M6-") (class "Default")
      (node (ref "U37") (pin "7") (pinfunction "BO2_7") (pintype "unspecified"))
      (node (ref "U37") (pin "8") (pinfunction "BO2_8") (pintype "unspecified"))
      (node (ref "U43") (pin "2") (pinfunction "2_2") (pintype "unspecified"))
    )
    (net (code "49") (name "M6_EN") (class "Default")
      (node (ref "R51") (pin "2") (pinfunction "2_2") (pintype "input"))
      (node (ref "U18") (pin "18") (pinfunction "GPIO15_18") (pintype "bidirectional"))
      (node (ref "U37") (pin "15") (pinfunction "PWMB_15") (pintype "unspecified"))
    )
    (net (code "50") (name "M7+") (class "Default")
      (node (ref "U35") (pin "1") (pinfunction "AO1_1") (pintype "unspecified"))
      (node (ref "U35") (pin "2") (pinfunction "AO1_2") (pintype "unspecified"))
      (node (ref "U44") (pin "1") (pinfunction "1_1") (pintype "unspecified"))
    )
    (net (code "51") (name "M7-") (class "Default")
      (node (ref "U35") (pin "5") (pinfunction "AO2_5") (pintype "unspecified"))
      (node (ref "U35") (pin "6") (pinfunction "AO2_6") (pintype "unspecified"))
      (node (ref "U44") (pin "2") (pinfunction "2_2") (pintype "unspecified"))
    )
    (net (code "52") (name "M7_EN") (class "Default")
      (node (ref "R46") (pin "2") (pinfunction "2_2") (pintype "input"))
      (node (ref "U18") (pin "27") (pinfunction "GPIO16_27") (pintype "bidirectional"))
      (node (ref "U35") (pin "23") (pinfunction "PWMA_23") (pintype "unspecified"))
    )
    (net (code "53") (name "M8+") (class "Default")
      (node (ref "U35") (pin "11") (pinfunction "BO1_11") (pintype "unspecified"))
      (node (ref "U35") (pin "12") (pinfunction "BO1_12") (pintype "unspecified"))
      (node (ref "U45") (pin "1") (pinfunction "1_1") (pintype "unspecified"))
    )
    (net (code "54") (name "M8-") (class "Default")
      (node (ref "U35") (pin "7") (pinfunction "BO2_7") (pintype "unspecified"))
      (node (ref "U35") (pin "8") (pinfunction "BO2_8") (pintype "unspecified"))
      (node (ref "U45") (pin "2") (pinfunction "2_2") (pintype "unspecified"))
    )
    (net (code "55") (name "M8_EN") (class "Default")
      (node (ref "R52") (pin "2") (pinfunction "2_2") (pintype "input"))
      (node (ref "U18") (pin "28") (pinfunction "GPIO17_28") (pintype "bidirectional"))
      (node (ref "U35") (pin "15") (pinfunction "PWMB_15") (pintype "unspecified"))
    )
    (net (code "56") (name "M_VCC") (class "Default")
      (node (ref "C31") (pin "1") (pinfunction "1_1") (pintype "input"))
      (node (ref "C36") (pin "2") (pinfunction "2_2") (pintype "unspecified"))
      (node (ref "C37") (pin "2") (pinfunction "2_2") (pintype "unspecified"))
      (node (ref "C38") (pin "2") (pinfunction "2_2") (pintype "input"))
      (node (ref "C39") (pin "2") (pinfunction "2_2") (pintype "unspecified"))
      (node (ref "C40") (pin "2") (pinfunction "2_2") (pintype "unspecified"))
      (node (ref "C41") (pin "2") (pinfunction "2_2") (pintype "input"))
      (node (ref "C42") (pin "2") (pinfunction "2_2") (pintype "input"))
      (node (ref "C43") (pin "2") (pinfunction "2_2") (pintype "input"))
      (node (ref "R29") (pin "2") (pinfunction "2_2") (pintype "unspecified"))
      (node (ref "R34") (pin "1") (pinfunction "1_1") (pintype "input"))
      (node (ref "U34") (pin "13") (pinfunction "VM2_13") (pintype "unspecified"))
      (node (ref "U34") (pin "14") (pinfunction "VM3_14") (pintype "unspecified"))
      (node (ref "U34") (pin "24") (pinfunction "VM1_24") (pintype "unspecified"))
      (node (ref "U35") (pin "13") (pinfunction "VM2_13") (pintype "unspecified"))
      (node (ref "U35") (pin "14") (pinfunction "VM3_14") (pintype "unspecified"))
      (node (ref "U35") (pin "24") (pinfunction "VM1_24") (pintype "unspecified"))
      (node (ref "U36") (pin "13") (pinfunction "VM2_13") (pintype "unspecified"))
      (node (ref "U36") (pin "14") (pinfunction "VM3_14") (pintype "unspecified"))
      (node (ref "U36") (pin "24") (pinfunction "VM1_24") (pintype "unspecified"))
      (node (ref "U37") (pin "13") (pinfunction "VM2_13") (pintype "unspecified"))
      (node (ref "U37") (pin "14") (pinfunction "VM3_14") (pintype "unspecified"))
      (node (ref "U37") (pin "24") (pinfunction "VM1_24") (pintype "unspecified"))
    )
    (net (code "57") (name "Net-(C8-Pad1)") (class "Default")
      (node (ref "C8") (pin "1") (pinfunction "1_1") (pintype "unspecified"))
      (node (ref "R11") (pin "2") (pinfunction "2_2") (pintype "input"))
    )
    (net (code "58") (name "Net-(C10-Pad1)") (class "Default")
      (node (ref "C10") (pin "1") (pinfunction "1_1") (pintype "unspecified"))
      (node (ref "R13") (pin "2") (pinfunction "2_2") (pintype "input"))
    )
    (net (code "59") (name "Net-(D1-K)") (class "Default")
      (node (ref "D1") (pin "1") (pinfunction "K_1") (pintype "unspecified"))
      (node (ref "U6") (pin "1") (pinfunction "+Vin_1") (pintype "unspecified"))
    )
    (net (code "60") (name "Net-(LCD1-BLK)") (class "Default")
      (node (ref "LCD1") (pin "16") (pinfunction "BLK_16") (pintype "unspecified"))
      (node (ref "Q2") (pin "3") (pinfunction "3_3") (pintype "input"))
    )
    (net (code "61") (name "Net-(LCD1-DB4)") (class "Default")
      (node (ref "LCD1") (pin "11") (pinfunction "DB4_11") (pintype "unspecified"))
      (node (ref "U29") (pin "9") (pinfunction "P4_9") (pintype "unspecified"))
    )
    (net (code "62") (name "Net-(LCD1-DB5)") (class "Default")
      (node (ref "LCD1") (pin "12") (pinfunction "DB5_12") (pintype "unspecified"))
      (node (ref "U29") (pin "10") (pinfunction "P5_10") (pintype "unspecified"))
    )
    (net (code "63") (name "Net-(LCD1-DB6)") (class "Default")
      (node (ref "LCD1") (pin "13") (pinfunction "DB6_13") (pintype "unspecified"))
      (node (ref "U29") (pin "11") (pinfunction "P6_11") (pintype "unspecified"))
    )
    (net (code "64") (name "Net-(LCD1-DB7)") (class "Default")
      (node (ref "LCD1") (pin "14") (pinfunction "DB7_14") (pintype "unspecified"))
      (node (ref "U29") (pin "12") (pinfunction "P7_12") (pintype "unspecified"))
    )
    (net (code "65") (name "Net-(LCD1-E)") (class "Default")
      (node (ref "LCD1") (pin "6") (pinfunction "E_6") (pintype "unspecified"))
      (node (ref "U29") (pin "6") (pinfunction "P2_6") (pintype "unspecified"))
    )
    (net (code "66") (name "Net-(LCD1-RS)") (class "Default")
      (node (ref "LCD1") (pin "4") (pinfunction "RS_4") (pintype "unspecified"))
      (node (ref "U29") (pin "4") (pinfunction "P0_4") (pintype "unspecified"))
    )
    (net (code "67") (name "Net-(LCD1-RW)") (class "Default")
      (node (ref "LCD1") (pin "5") (pinfunction "RW_5") (pintype "unspecified"))
      (node (ref "U29") (pin "5") (pinfunction "P1_5") (pintype "unspecified"))
    )
    (net (code "68") (name "Net-(LCD1-V0)") (class "Default")
      (node (ref "LCD1") (pin "3") (pinfunction "V0_3") (pintype "unspecified"))
      (node (ref "R55") (pin "1") (pinfunction "1_1") (pintype "unspecified"))
    )
    (net (code "69") (name "Net-(LED1-+)") (class "Default")
      (node (ref "LED1") (pin "1") (pinfunction "+_1") (pintype "unspecified"))
      (node (ref "R4") (pin "1") (pinfunction "1_1") (pintype "input"))
    )
    (net (code "70") (name "Net-(LED2-+)") (class "Default")
      (node (ref "LED2") (pin "1") (pinfunction "+_1") (pintype "unspecified"))
      (node (ref "R7") (pin "1") (pinfunction "1_1") (pintype "input"))
    )
    (net (code "71") (name "Net-(LED3-+)") (class "Default")
      (node (ref "LED3") (pin "1") (pinfunction "+_1") (pintype "unspecified"))
      (node (ref "R10") (pin "1") (pinfunction "1_1") (pintype "input"))
    )
    (net (code "72") (name "Net-(LED4-+)") (class "Default")
      (node (ref "LED4") (pin "1") (pinfunction "+_1") (pintype "unspecified"))
      (node (ref "R32") (pin "1") (pinfunction "1_1") (pintype "input"))
    )
    (net (code "73") (name "Net-(LED5-+)") (class "Default")
      (node (ref "LED5") (pin "1") (pinfunction "+_1") (pintype "unspecified"))
      (node (ref "R39") (pin "1") (pinfunction "1_1") (pintype "input"))
    )
    (net (code "74") (name "Net-(LED6-+)") (class "Default")
      (node (ref "LED6") (pin "1") (pinfunction "+_1") (pintype "unspecified"))
      (node (ref "R40") (pin "1") (pinfunction "1_1") (pintype "input"))
    )
    (net (code "75") (name "Net-(LED7-+)") (class "Default")
      (node (ref "LED7") (pin "1") (pinfunction "+_1") (pintype "unspecified"))
      (node (ref "R41") (pin "1") (pinfunction "1_1") (pintype "input"))
    )
    (net (code "76") (name "Net-(LED8-+)") (class "Default")
      (node (ref "LED8") (pin "1") (pinfunction "+_1") (pintype "unspecified"))
      (node (ref "R43") (pin "1") (pinfunction "1_1") (pintype "input"))
    )
    (net (code "77") (name "Net-(LED9-+)") (class "Default")
      (node (ref "LED9") (pin "1") (pinfunction "+_1") (pintype "unspecified"))
      (node (ref "R45") (pin "1") (pinfunction "1_1") (pintype "input"))
    )
    (net (code "78") (name "Net-(LED10-+)") (class "Default")
      (node (ref "LED10") (pin "1") (pinfunction "+_1") (pintype "unspecified"))
      (node (ref "R46") (pin "1") (pinfunction "1_1") (pintype "input"))
    )
    (net (code "79") (name "Net-(LED11-+)") (class "Default")
      (node (ref "LED11") (pin "1") (pinfunction "+_1") (pintype "unspecified"))
      (node (ref "R47") (pin "1") (pinfunction "1_1") (pintype "input"))
    )
    (net (code "80") (name "Net-(LED12-+)") (class "Default")
      (node (ref "LED12") (pin "1") (pinfunction "+_1") (pintype "unspecified"))
      (node (ref "R48") (pin "1") (pinfunction "1_1") (pintype "input"))
    )
    (net (code "81") (name "Net-(LED13-+)") (class "Default")
      (node (ref "LED13") (pin "1") (pinfunction "+_1") (pintype "unspecified"))
      (node (ref "R51") (pin "1") (pinfunction "1_1") (pintype "input"))
    )
    (net (code "82") (name "Net-(LED14-+)") (class "Default")
      (node (ref "LED14") (pin "1") (pinfunction "+_1") (pintype "unspecified"))
      (node (ref "R52") (pin "1") (pinfunction "1_1") (pintype "input"))
    )
    (net (code "83") (name "Net-(LED15-+)") (class "Default")
      (node (ref "LED15") (pin "1") (pinfunction "+_1") (pintype "unspecified"))
      (node (ref "R53") (pin "1") (pinfunction "1_1") (pintype "input"))
    )
    (net (code "84") (name "Net-(LED16-+)") (class "Default")
      (node (ref "LED16") (pin "1") (pinfunction "+_1") (pintype "unspecified"))
      (node (ref "R54") (pin "1") (pinfunction "1_1") (pintype "input"))
    )
    (net (code "85") (name "Net-(Q1-D)") (class "Default")
      (node (ref "JMP1") (pin "2") (pinfunction "2_2") (pintype "unspecified"))
      (node (ref "Q1") (pin "3") (pinfunction "D_3") (pintype "unspecified"))
      (node (ref "R9") (pin "2") (pinfunction "2_2") (pintype "input"))
    )
    (net (code "86") (name "Net-(R12-Pad2)") (class "Default")
      (node (ref "R12") (pin "2") (pinfunction "2_2") (pintype "input"))
      (node (ref "SW1") (pin "1") (pinfunction "1_1") (pintype "unspecified"))
    )
    (net (code "87") (name "Net-(R21-Pad2)") (class "Default")
      (node (ref "R21") (pin "2") (pinfunction "2_2") (pintype "input"))
      (node (ref "SW3") (pin "D") (pinfunction "D_D") (pintype "unspecified"))
    )
    (net (code "88") (name "Net-(U9-VREF)") (class "Default")
      (node (ref "C3") (pin "2") (pinfunction "2_2") (pintype "input"))
      (node (ref "U9") (pin "8") (pinfunction "VREF_8") (pintype "unspecified"))
    )
    (net (code "89") (name "Net-(U18-USB_DM)") (class "Default")
      (node (ref "R18") (pin "2") (pinfunction "2_2") (pintype "input"))
      (node (ref "U18") (pin "46") (pinfunction "USB_DM_46") (pintype "bidirectional"))
    )
    (net (code "90") (name "Net-(U18-USB_DP)") (class "Default")
      (node (ref "R16") (pin "2") (pinfunction "2_2") (pintype "input"))
      (node (ref "U18") (pin "47") (pinfunction "USB_DP_47") (pintype "bidirectional"))
    )
    (net (code "91") (name "Net-(U18-XIN)") (class "Default")
      (node (ref "C29") (pin "2") (pinfunction "2_2") (pintype "input"))
      (node (ref "U18") (pin "20") (pinfunction "XIN_20") (pintype "input"))
      (node (ref "X1") (pin "1") (pinfunction "OSC1_1") (pintype "input"))
    )
    (net (code "92") (name "Net-(U18-XOUT)") (class "Default")
      (node (ref "C30") (pin "2") (pinfunction "2_2") (pintype "input"))
      (node (ref "U18") (pin "21") (pinfunction "XOUT_21") (pintype "unspecified"))
      (node (ref "X1") (pin "2") (pinfunction "OSC2_2") (pintype "input"))
    )
    (net (code "93") (name "Net-(U23-IN+)") (class "Default")
      (node (ref "R33") (pin "2") (pinfunction "2_2") (pintype "input"))
      (node (ref "U23") (pin "8") (pinfunction "IN+_8") (pintype "unspecified"))
    )
    (net (code "94") (name "Net-(U23-IN-)") (class "Default")
      (node (ref "R34") (pin "2") (pinfunction "2_2") (pintype "input"))
      (node (ref "U23") (pin "7") (pinfunction "IN-_7") (pintype "unspecified"))
    )
    (net (code "95") (name "Net-(U29-P3)") (class "Default")
      (node (ref "Q2") (pin "1") (pinfunction "1_1") (pintype "input"))
      (node (ref "R49") (pin "1") (pinfunction "1_1") (pintype "input"))
      (node (ref "U29") (pin "7") (pinfunction "P3_7") (pintype "unspecified"))
    )
    (net (code "96") (name "Net-(USB1-CC1)") (class "Default")
      (node (ref "R3") (pin "2") (pinfunction "2_2") (pintype "input"))
      (node (ref "USB1") (pin "4") (pinfunction "CC1_4") (pintype "unspecified"))
    )
    (net (code "97") (name "Net-(USB1-CC2)") (class "Default")
      (node (ref "R1") (pin "2") (pinfunction "2_2") (pintype "input"))
      (node (ref "USB1") (pin "10") (pinfunction "CC2_10") (pintype "unspecified"))
    )
    (net (code "98") (name "Prog_BTN") (class "Default")
      (node (ref "R31") (pin "1") (pinfunction "1_1") (pintype "input"))
      (node (ref "SW4") (pin "1") (pinfunction "1_1") (pintype "unspecified"))
      (node (ref "U18") (pin "36") (pinfunction "GPIO24_36") (pintype "bidirectional"))
    )
    (net (code "99") (name "Prog_LED") (class "Default")
      (node (ref "R40") (pin "2") (pinfunction "2_2") (pintype "input"))
      (node (ref "U18") (pin "35") (pinfunction "GPIO23_35") (pintype "bidirectional"))
    )
    (net (code "100") (name "QSPI_SCK") (class "Default")
      (node (ref "U16") (pin "6") (pinfunction "CLK_6") (pintype "unspecified"))
      (node (ref "U18") (pin "52") (pinfunction "QSPI_SCLK_52") (pintype "output"))
    )
    (net (code "101") (name "QSPI_SD0") (class "Default")
      (node (ref "U16") (pin "5") (pinfunction "DI(IO0)_5") (pintype "unspecified"))
      (node (ref "U18") (pin "53") (pinfunction "QSPI_SD0_53") (pintype "bidirectional"))
    )
    (net (code "102") (name "QSPI_SD1") (class "Default")
      (node (ref "U16") (pin "2") (pinfunction "DO(IO1)_2") (pintype "unspecified"))
      (node (ref "U18") (pin "55") (pinfunction "QSPI_SD1_55") (pintype "bidirectional"))
    )
    (net (code "103") (name "QSPI_SD2") (class "Default")
      (node (ref "U16") (pin "3") (pinfunction "/WP(IO2)_3") (pintype "unspecified"))
      (node (ref "U18") (pin "54") (pinfunction "QSPI_SD2_54") (pintype "bidirectional"))
    )
    (net (code "104") (name "QSPI_SD3") (class "Default")
      (node (ref "U16") (pin "7") (pinfunction "/HOLDor/RESET(IO3)_7") (pintype "unspecified"))
      (node (ref "U18") (pin "51") (pinfunction "QSPI_SD3_51") (pintype "bidirectional"))
    )
    (net (code "105") (name "QSPI_SS") (class "Default")
      (node (ref "R12") (pin "1") (pinfunction "1_1") (pintype "input"))
      (node (ref "R8") (pin "2") (pinfunction "2_2") (pintype "input"))
      (node (ref "U16") (pin "1") (pinfunction "/CS_1") (pintype "unspecified"))
      (node (ref "U18") (pin "56") (pinfunction "QSPI_SS_56") (pintype "bidirectional"))
    )
    (net (code "106") (name "R68") (class "Default")
      (node (ref "U11") (pin "1") (pinfunction "1_1") (pintype "unspecified"))
      (node (ref "U9") (pin "3") (pinfunction "R68_3") (pintype "unspecified"))
    )
    (net (code "107") (name "RUN") (class "Default")
      (node (ref "R6") (pin "2") (pinfunction "2_2") (pintype "input"))
      (node (ref "SW2") (pin "1") (pinfunction "1_1") (pintype "unspecified"))
      (node (ref "U18") (pin "26") (pinfunction "RUN_26") (pintype "input"))
    )
    (net (code "108") (name "RxD") (class "Default")
      (node (ref "CN1") (pin "2") (pinfunction "2_2") (pintype "unspecified"))
      (node (ref "U25") (pin "8") (pinfunction "TOSC1/PB3_8") (pintype "unspecified"))
    )
    (net (code "109") (name "SCL") (class "Default")
      (node (ref "R28") (pin "1") (pinfunction "1_1") (pintype "input"))
      (node (ref "U18") (pin "7") (pinfunction "GPIO5_7") (pintype "bidirectional"))
      (node (ref "U23") (pin "4") (pinfunction "SCL_4") (pintype "unspecified"))
      (node (ref "U29") (pin "14") (pinfunction "SCL_14") (pintype "unspecified"))
    )
    (net (code "110") (name "SDA") (class "Default")
      (node (ref "R24") (pin "1") (pinfunction "1_1") (pintype "input"))
      (node (ref "U18") (pin "6") (pinfunction "GPIO4_6") (pintype "bidirectional"))
      (node (ref "U23") (pin "3") (pinfunction "SDA_3") (pintype "unspecified"))
      (node (ref "U29") (pin "15") (pinfunction "SDA_15") (pintype "unspecified"))
    )
    (net (code "111") (name "SWC") (class "Default")
      (node (ref "S1") (pin "1") (pinfunction "1_1") (pintype "unspecified"))
      (node (ref "U18") (pin "24") (pinfunction "SWCLK_24") (pintype "output"))
    )
    (net (code "112") (name "SWD") (class "Default")
      (node (ref "S1") (pin "3") (pinfunction "3_3") (pintype "unspecified"))
      (node (ref "U18") (pin "25") (pinfunction "SWD_25") (pintype "bidirectional"))
    )
    (net (code "113") (name "T0") (class "Default")
      (node (ref "R25") (pin "1") (pinfunction "1_1") (pintype "input"))
      (node (ref "U17") (pin "2") (pinfunction "2_2") (pintype "unspecified"))
      (node (ref "U25") (pin "3") (pinfunction "PA5_3") (pintype "unspecified"))
    )
    (net (code "114") (name "T1") (class "Default")
      (node (ref "R30") (pin "1") (pinfunction "1_1") (pintype "input"))
      (node (ref "U19") (pin "2") (pinfunction "2_2") (pintype "unspecified"))
      (node (ref "U25") (pin "4") (pinfunction "PA6_4") (pintype "unspecified"))
    )
    (net (code "115") (name "T2") (class "Default")
      (node (ref "R35") (pin "1") (pinfunction "1_1") (pintype "input"))
      (node (ref "U22") (pin "2") (pinfunction "2_2") (pintype "unspecified"))
      (node (ref "U25") (pin "5") (pinfunction "PA7_5") (pintype "unspecified"))
    )
    (net (code "116") (name "T3") (class "Default")
      (node (ref "R38") (pin "1") (pinfunction "1_1") (pintype "input"))
      (node (ref "U24") (pin "2") (pinfunction "2_2") (pintype "unspecified"))
      (node (ref "U25") (pin "6") (pinfunction "PB5_6") (pintype "unspecified"))
    )
    (net (code "117") (name "T4") (class "Default")
      (node (ref "R42") (pin "1") (pinfunction "1_1") (pintype "input"))
      (node (ref "U25") (pin "7") (pinfunction "PB4_7") (pintype "unspecified"))
      (node (ref "U27") (pin "2") (pinfunction "2_2") (pintype "unspecified"))
    )
    (net (code "118") (name "T5") (class "Default")
      (node (ref "R44") (pin "1") (pinfunction "1_1") (pintype "input"))
      (node (ref "U25") (pin "10") (pinfunction "PB1_10") (pintype "unspecified"))
      (node (ref "U30") (pin "2") (pinfunction "2_2") (pintype "unspecified"))
    )
    (net (code "119") (name "T6") (class "Default")
      (node (ref "R50") (pin "1") (pinfunction "1_1") (pintype "input"))
      (node (ref "U25") (pin "13") (pinfunction "PC1_13") (pintype "unspecified"))
      (node (ref "U31") (pin "2") (pinfunction "2_2") (pintype "unspecified"))
    )
    (net (code "120") (name "T7") (class "Default")
      (node (ref "R56") (pin "1") (pinfunction "1_1") (pintype "input"))
      (node (ref "U25") (pin "12") (pinfunction "PC0_12") (pintype "unspecified"))
      (node (ref "U32") (pin "2") (pinfunction "2_2") (pintype "unspecified"))
    )
    (net (code "121") (name "T8") (class "Default")
      (node (ref "R57") (pin "1") (pinfunction "1_1") (pintype "input"))
      (node (ref "U25") (pin "11") (pinfunction "PB0_11") (pintype "unspecified"))
      (node (ref "U33") (pin "2") (pinfunction "2_2") (pintype "unspecified"))
    )
    (net (code "122") (name "T_INT") (class "Default")
      (node (ref "R20") (pin "1") (pinfunction "1_1") (pintype "input"))
      (node (ref "U18") (pin "34") (pinfunction "GPIO22_34") (pintype "bidirectional"))
      (node (ref "U25") (pin "14") (pinfunction "PC2_14") (pintype "unspecified"))
    )
    (net (code "123") (name "T_Rx") (class "Default")
      (node (ref "R37") (pin "1") (pinfunction "1_1") (pintype "input"))
      (node (ref "U18") (pin "12") (pinfunction "GPIO9_12") (pintype "bidirectional"))
      (node (ref "U25") (pin "17") (pinfunction "PA1_17") (pintype "unspecified"))
      (node (ref "U28") (pin "1") (pinfunction "1_1") (pintype "unspecified"))
    )
    (net (code "124") (name "T_Tx") (class "Default")
      (node (ref "R36") (pin "1") (pinfunction "1_1") (pintype "input"))
      (node (ref "U18") (pin "11") (pinfunction "GPIO8_11") (pintype "bidirectional"))
      (node (ref "U25") (pin "18") (pinfunction "PA2_18") (pintype "unspecified"))
      (node (ref "U26") (pin "1") (pinfunction "1_1") (pintype "unspecified"))
    )
    (net (code "125") (name "TxD") (class "Default")
      (node (ref "CN1") (pin "4") (pinfunction "4_4") (pintype "unspecified"))
      (node (ref "U25") (pin "9") (pinfunction "TOSC2/PB2_9") (pintype "unspecified"))
    )
    (net (code "126") (name "UPDI") (class "Default")
      (node (ref "CN1") (pin "3") (pinfunction "3_3") (pintype "unspecified"))
      (node (ref "U25") (pin "16") (pinfunction "PA0/RESET#/UPDI_16") (pintype "unspecified"))
    )
    (net (code "127") (name "USB_VCC") (class "Default")
      (node (ref "D6") (pin "2") (pinfunction "A_2") (pintype "unspecified"))
      (node (ref "Q1") (pin "1") (pinfunction "G_1") (pintype "unspecified"))
      (node (ref "R5") (pin "1") (pinfunction "1_1") (pintype "input"))
      (node (ref "USB1") (pin "11") (pinfunction "VBUS_11") (pintype "unspecified"))
      (node (ref "USB1") (pin "2") (pinfunction "VBUS_2") (pintype "unspecified"))
    )
    (net (code "128") (name "VCC") (class "Default")
      (node (ref "C1") (pin "2") (pinfunction "2_2") (pintype "input"))
      (node (ref "U9") (pin "20") (pinfunction "VCCCORE_20") (pintype "unspecified"))
    )
    (net (code "129") (name "VCC_OK") (class "Default")
      (node (ref "R4") (pin "2") (pinfunction "2_2") (pintype "input"))
      (node (ref "U18") (pin "5") (pinfunction "GPIO3_5") (pintype "bidirectional"))
      (node (ref "U9") (pin "19") (pinfunction "VCC_OK_19") (pintype "unspecified"))
    )
    (net (code "130") (name "VDDHV") (class "Default")
      (node (ref "C12") (pin "1") (pinfunction "1_1") (pintype "input"))
      (node (ref "C5") (pin "1") (pinfunction "1_1") (pintype "input"))
      (node (ref "C9") (pin "1") (pinfunction "1_1") (pintype "unspecified"))
      (node (ref "U10") (pin "1") (pinfunction "K_1") (pintype "unspecified"))
      (node (ref "U9") (pin "1") (pinfunction "VDD_REGIN_1") (pintype "unspecified"))
      (node (ref "U9") (pin "14") (pinfunction "DCDC_IN_14") (pintype "unspecified"))
      (node (ref "U9") (pin "9") (pinfunction "VDDHV_9") (pintype "unspecified"))
    )
    (net (code "131") (name "VDDHV_PD") (class "Default")
      (node (ref "U10") (pin "2") (pinfunction "A_2") (pintype "unspecified"))
      (node (ref "U9") (pin "10") (pinfunction "VDDHV_PD_10") (pintype "unspecified"))
    )
    (net (code "132") (name "VFLT") (class "Default")
      (node (ref "C5") (pin "2") (pinfunction "2_2") (pintype "input"))
      (node (ref "C7") (pin "2") (pinfunction "2_2") (pintype "input"))
      (node (ref "U9") (pin "7") (pinfunction "VFLT_7") (pintype "unspecified"))
    )
    (net (code "133") (name "VGATE") (class "Default")
      (node (ref "C6") (pin "2") (pinfunction "2_2") (pintype "input"))
      (node (ref "U9") (pin "13") (pinfunction "VGATE_13") (pintype "unspecified"))
    )
    (net (code "134") (name "unconnected-(R55-Pad3)") (class "Default")
      (node (ref "R55") (pin "3") (pinfunction "3_3") (pintype "unspecified+no_connect"))
    )
    (net (code "135") (name "unconnected-(SW3-EH-Pad6)") (class "Default")
      (node (ref "SW3") (pin "6") (pinfunction "EH_6") (pintype "unspecified+no_connect"))
    )
    (net (code "136") (name "unconnected-(SW3-EH-Pad7)") (class "Default")
      (node (ref "SW3") (pin "7") (pinfunction "EH_7") (pintype "unspecified+no_connect"))
    )
    (net (code "137") (name "unconnected-(U18-GPIO26_ADC0-Pad38)") (class "Default")
      (node (ref "U18") (pin "38") (pinfunction "GPIO26_ADC0_38") (pintype "bidirectional+no_connect"))
    )
    (net (code "138") (name "unconnected-(U18-GPIO27_ADC1-Pad39)") (class "Default")
      (node (ref "U18") (pin "39") (pinfunction "GPIO27_ADC1_39") (pintype "bidirectional+no_connect"))
    )
    (net (code "139") (name "unconnected-(U18-GPIO28_ADC2-Pad40)") (class "Default")
      (node (ref "U18") (pin "40") (pinfunction "GPIO28_ADC2_40") (pintype "bidirectional+no_connect"))
    )
    (net (code "140") (name "unconnected-(U18-GPIO29_ADC3-Pad41)") (class "Default")
      (node (ref "U18") (pin "41") (pinfunction "GPIO29_ADC3_41") (pintype "bidirectional+no_connect"))
    )
    (net (code "141") (name "unconnected-(U25-PA3{slash}EXTCLK-Pad19)") (class "Default")
      (node (ref "U25") (pin "19") (pinfunction "PA3/EXTCLK_19") (pintype "unspecified+no_connect"))
    )
    (net (code "142") (name "unconnected-(U29-INT#-Pad13)") (class "Default")
      (node (ref "U29") (pin "13") (pinfunction "INT#_13") (pintype "unspecified+no_connect"))
    )
    (net (code "143") (name "unconnected-(USB1-SBU1-Pad9)") (class "Default")
      (node (ref "USB1") (pin "9") (pinfunction "SBU1_9") (pintype "unspecified+no_connect"))
    )
    (net (code "144") (name "unconnected-(USB1-SBU2-Pad3)") (class "Default")
      (node (ref "USB1") (pin "3") (pinfunction "SBU2_3") (pintype "unspecified+no_connect"))
    )
  )
)
